# wordclock_frame_led_pcb.net
KiCad netlist of a schematic drawn in EAGLE
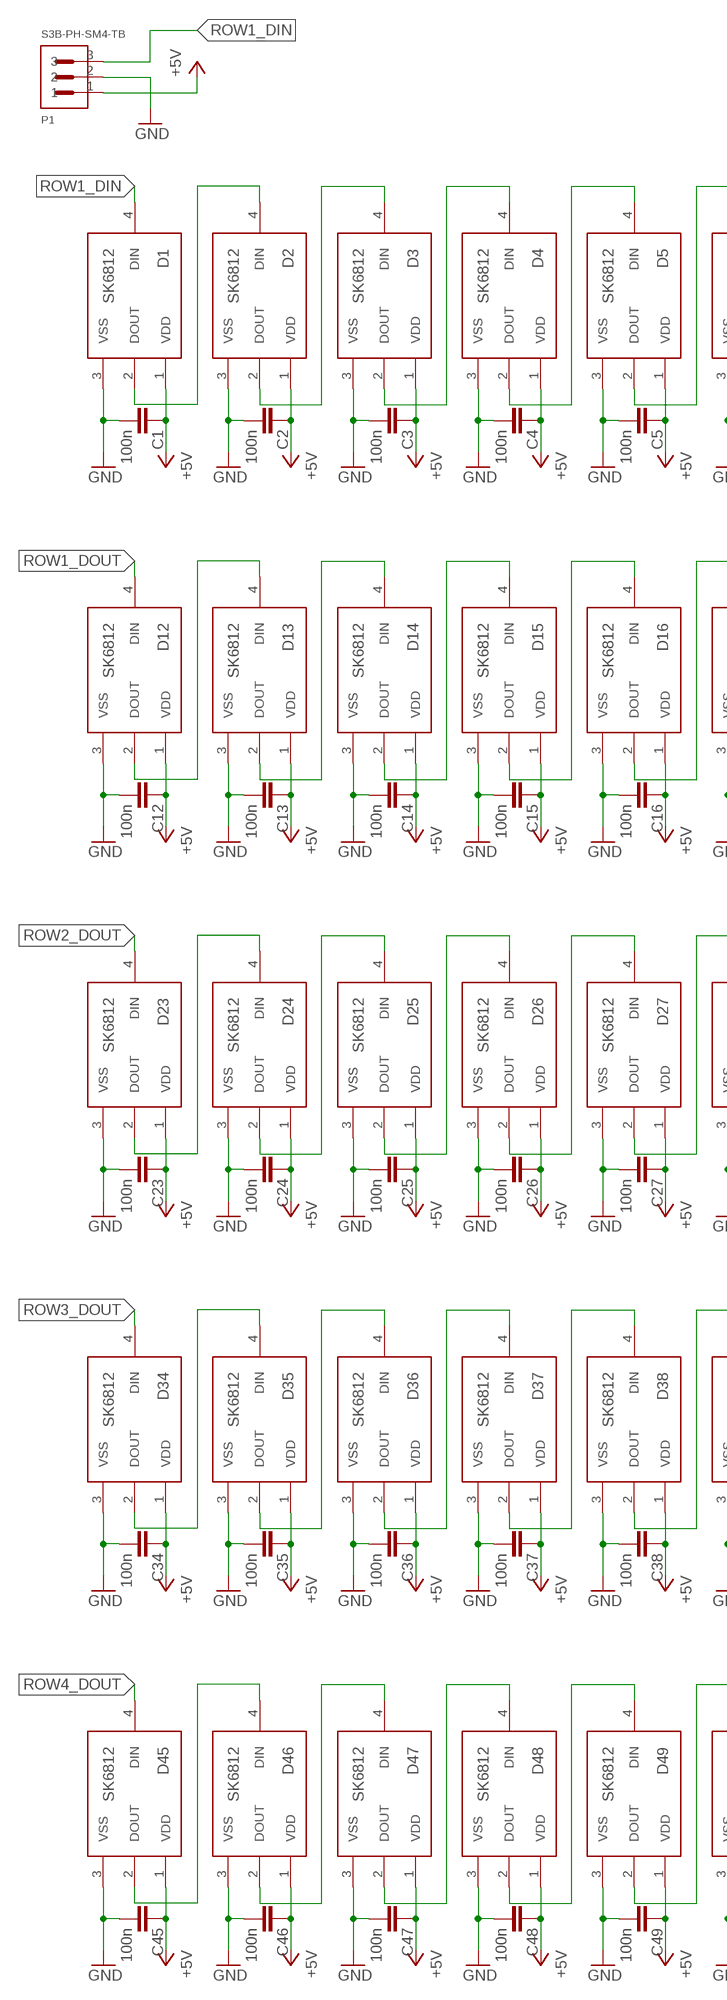
[diagram p0: schematic, sheet 1, part 1 of 2]
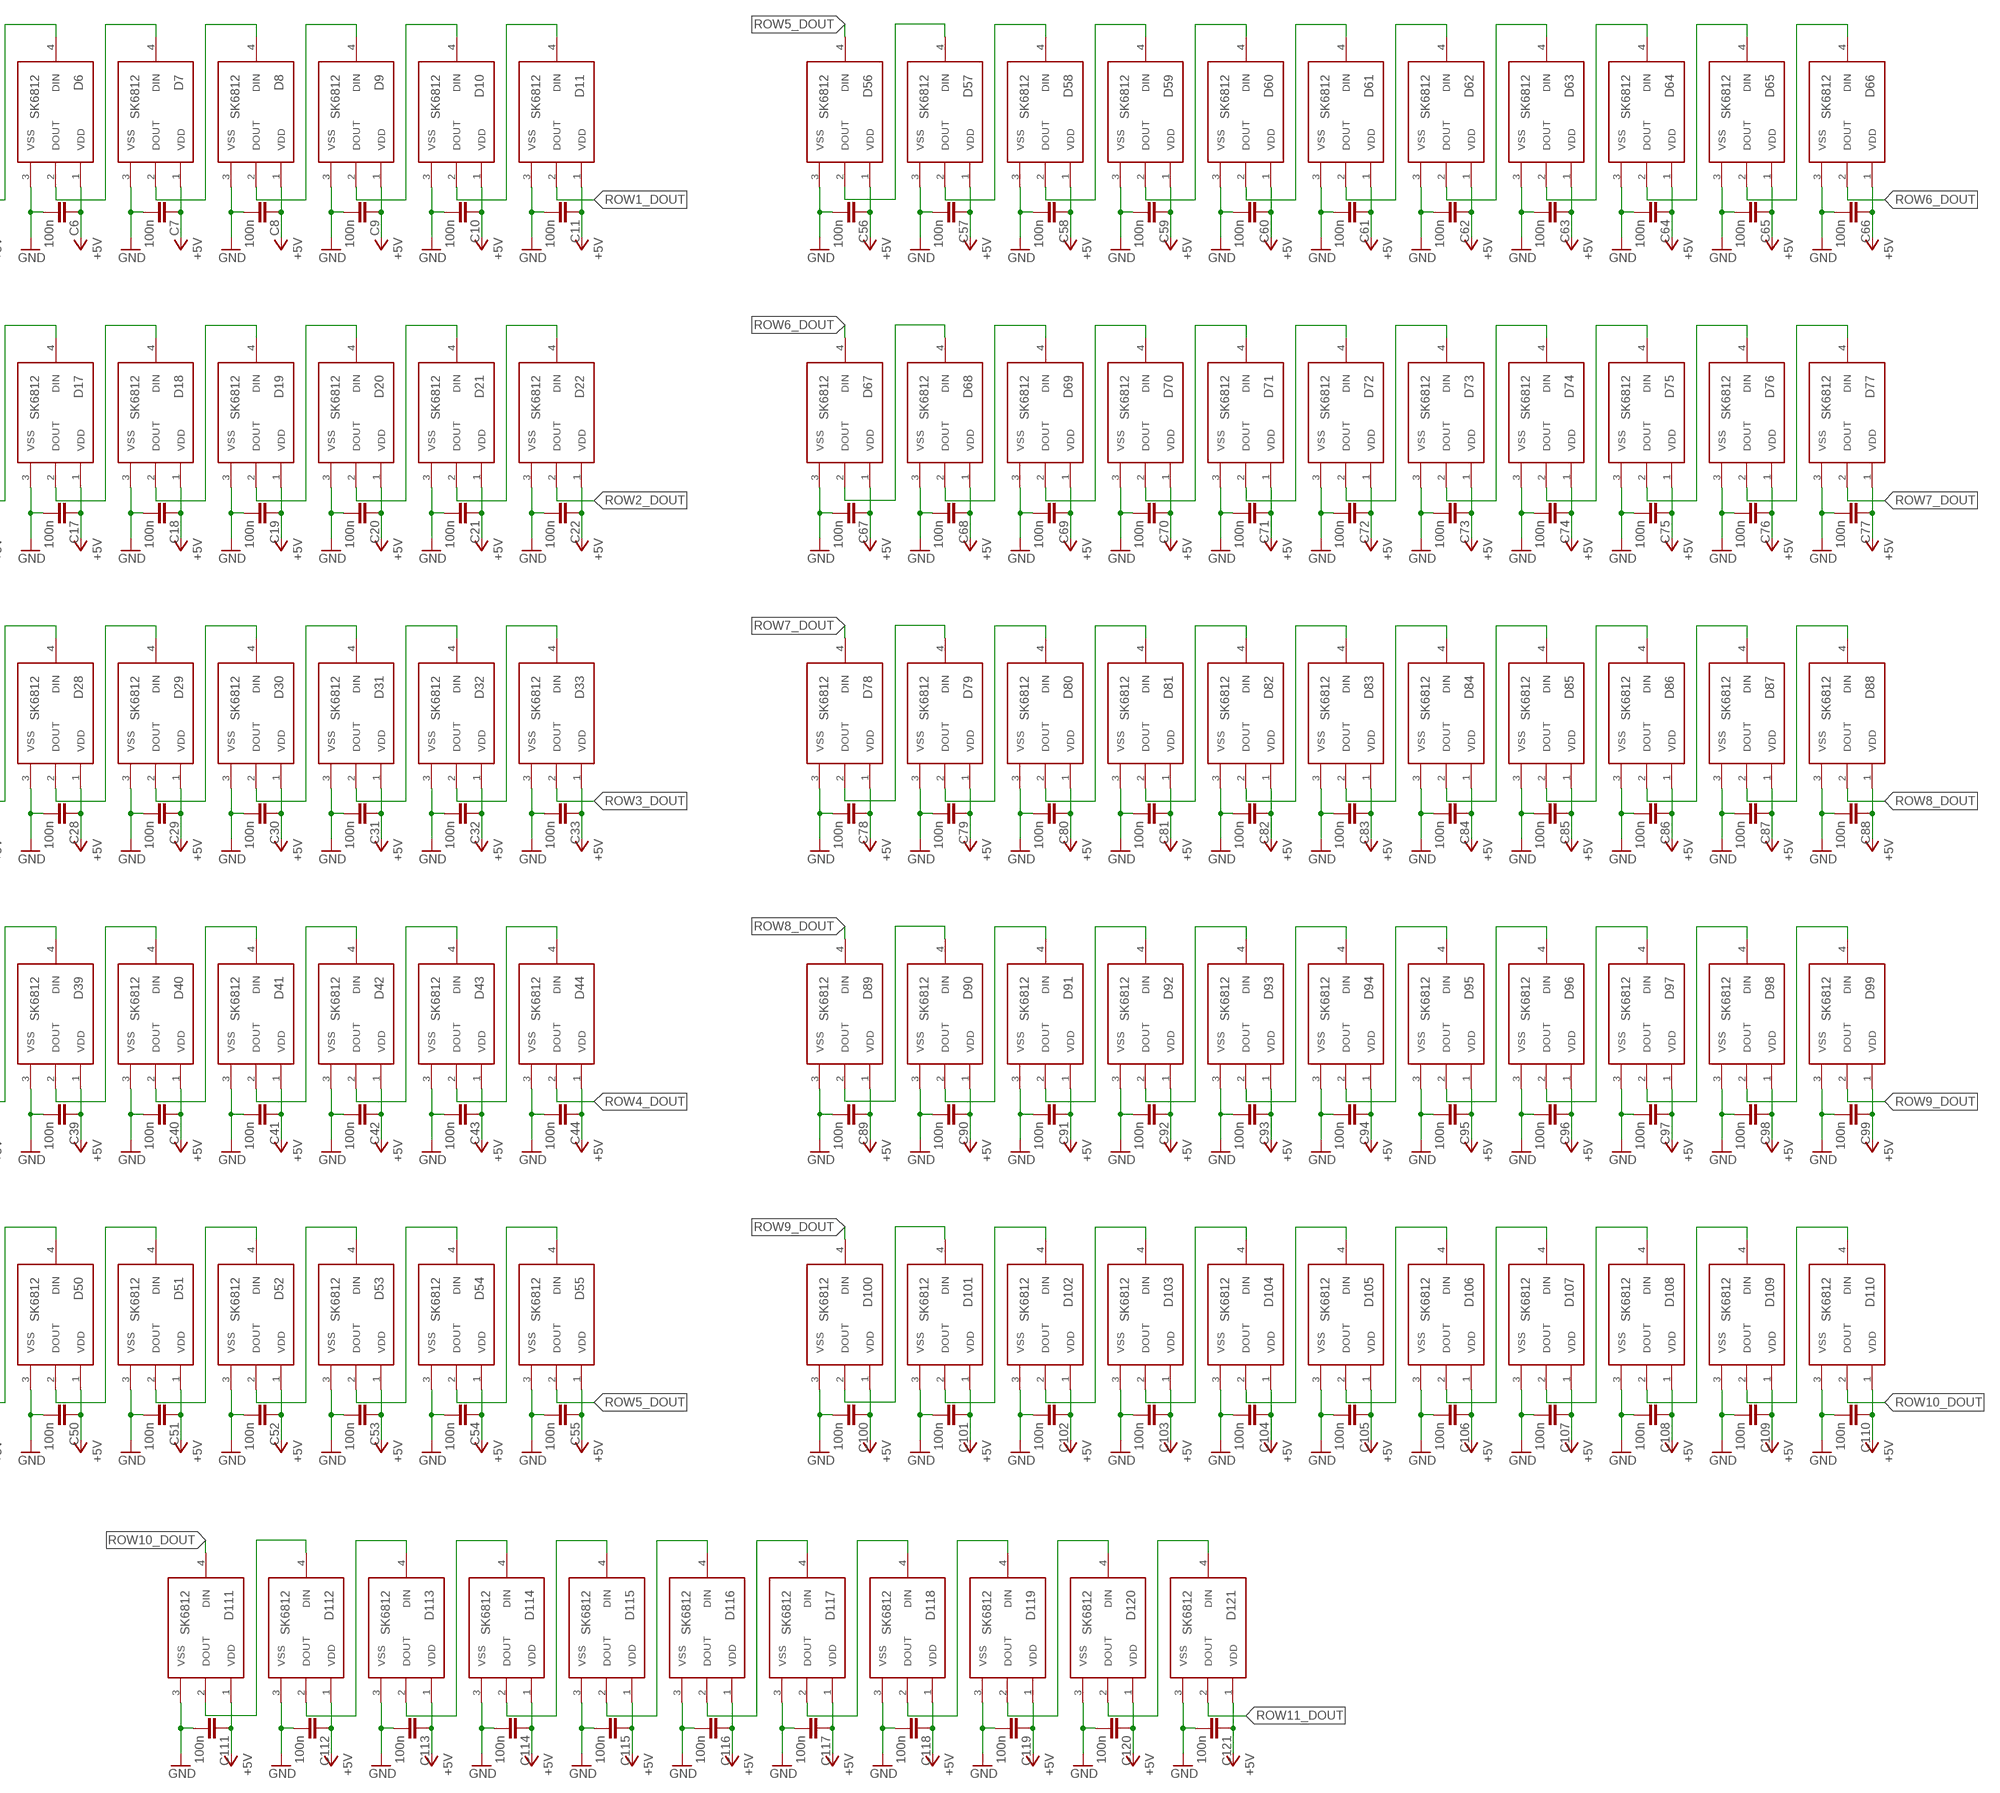
[diagram p1: schematic, sheet 1, part 2 of 2]

(export (version "E")
  (design (tool "Eeschema 10.0.6"))
  (components
    (comp (ref "C1")
      (value "100n")
      (footprint "eagle-import:C0603")
      (libsource (lib "eagle-import") (part "C-EUC0603"))
    )
    (comp (ref "C2")
      (value "100n")
      (footprint "eagle-import:C0603")
      (libsource (lib "eagle-import") (part "C-EUC0603"))
    )
    (comp (ref "C3")
      (value "100n")
      (footprint "eagle-import:C0603")
      (libsource (lib "eagle-import") (part "C-EUC0603"))
    )
    (comp (ref "C4")
      (value "100n")
      (footprint "eagle-import:C0603")
      (libsource (lib "eagle-import") (part "C-EUC0603"))
    )
    (comp (ref "C5")
      (value "100n")
      (footprint "eagle-import:C0603")
      (libsource (lib "eagle-import") (part "C-EUC0603"))
    )
    (comp (ref "C6")
      (value "100n")
      (footprint "eagle-import:C0603")
      (libsource (lib "eagle-import") (part "C-EUC0603"))
    )
    (comp (ref "C7")
      (value "100n")
      (footprint "eagle-import:C0603")
      (libsource (lib "eagle-import") (part "C-EUC0603"))
    )
    (comp (ref "C8")
      (value "100n")
      (footprint "eagle-import:C0603")
      (libsource (lib "eagle-import") (part "C-EUC0603"))
    )
    (comp (ref "C9")
      (value "100n")
      (footprint "eagle-import:C0603")
      (libsource (lib "eagle-import") (part "C-EUC0603"))
    )
    (comp (ref "C10")
      (value "100n")
      (footprint "eagle-import:C0603")
      (libsource (lib "eagle-import") (part "C-EUC0603"))
    )
    (comp (ref "C11")
      (value "100n")
      (footprint "eagle-import:C0603")
      (libsource (lib "eagle-import") (part "C-EUC0603"))
    )
    (comp (ref "C12")
      (value "100n")
      (footprint "eagle-import:C0603")
      (libsource (lib "eagle-import") (part "C-EUC0603"))
    )
    (comp (ref "C13")
      (value "100n")
      (footprint "eagle-import:C0603")
      (libsource (lib "eagle-import") (part "C-EUC0603"))
    )
    (comp (ref "C14")
      (value "100n")
      (footprint "eagle-import:C0603")
      (libsource (lib "eagle-import") (part "C-EUC0603"))
    )
    (comp (ref "C15")
      (value "100n")
      (footprint "eagle-import:C0603")
      (libsource (lib "eagle-import") (part "C-EUC0603"))
    )
    (comp (ref "C16")
      (value "100n")
      (footprint "eagle-import:C0603")
      (libsource (lib "eagle-import") (part "C-EUC0603"))
    )
    (comp (ref "C17")
      (value "100n")
      (footprint "eagle-import:C0603")
      (libsource (lib "eagle-import") (part "C-EUC0603"))
    )
    (comp (ref "C18")
      (value "100n")
      (footprint "eagle-import:C0603")
      (libsource (lib "eagle-import") (part "C-EUC0603"))
    )
    (comp (ref "C19")
      (value "100n")
      (footprint "eagle-import:C0603")
      (libsource (lib "eagle-import") (part "C-EUC0603"))
    )
    (comp (ref "C20")
      (value "100n")
      (footprint "eagle-import:C0603")
      (libsource (lib "eagle-import") (part "C-EUC0603"))
    )
    (comp (ref "C21")
      (value "100n")
      (footprint "eagle-import:C0603")
      (libsource (lib "eagle-import") (part "C-EUC0603"))
    )
    (comp (ref "C22")
      (value "100n")
      (footprint "eagle-import:C0603")
      (libsource (lib "eagle-import") (part "C-EUC0603"))
    )
    (comp (ref "C23")
      (value "100n")
      (footprint "eagle-import:C0603")
      (libsource (lib "eagle-import") (part "C-EUC0603"))
    )
    (comp (ref "C24")
      (value "100n")
      (footprint "eagle-import:C0603")
      (libsource (lib "eagle-import") (part "C-EUC0603"))
    )
    (comp (ref "C25")
      (value "100n")
      (footprint "eagle-import:C0603")
      (libsource (lib "eagle-import") (part "C-EUC0603"))
    )
    (comp (ref "C26")
      (value "100n")
      (footprint "eagle-import:C0603")
      (libsource (lib "eagle-import") (part "C-EUC0603"))
    )
    (comp (ref "C27")
      (value "100n")
      (footprint "eagle-import:C0603")
      (libsource (lib "eagle-import") (part "C-EUC0603"))
    )
    (comp (ref "C28")
      (value "100n")
      (footprint "eagle-import:C0603")
      (libsource (lib "eagle-import") (part "C-EUC0603"))
    )
    (comp (ref "C29")
      (value "100n")
      (footprint "eagle-import:C0603")
      (libsource (lib "eagle-import") (part "C-EUC0603"))
    )
    (comp (ref "C30")
      (value "100n")
      (footprint "eagle-import:C0603")
      (libsource (lib "eagle-import") (part "C-EUC0603"))
    )
    (comp (ref "C31")
      (value "100n")
      (footprint "eagle-import:C0603")
      (libsource (lib "eagle-import") (part "C-EUC0603"))
    )
    (comp (ref "C32")
      (value "100n")
      (footprint "eagle-import:C0603")
      (libsource (lib "eagle-import") (part "C-EUC0603"))
    )
    (comp (ref "C33")
      (value "100n")
      (footprint "eagle-import:C0603")
      (libsource (lib "eagle-import") (part "C-EUC0603"))
    )
    (comp (ref "C34")
      (value "100n")
      (footprint "eagle-import:C0603")
      (libsource (lib "eagle-import") (part "C-EUC0603"))
    )
    (comp (ref "C35")
      (value "100n")
      (footprint "eagle-import:C0603")
      (libsource (lib "eagle-import") (part "C-EUC0603"))
    )
    (comp (ref "C36")
      (value "100n")
      (footprint "eagle-import:C0603")
      (libsource (lib "eagle-import") (part "C-EUC0603"))
    )
    (comp (ref "C37")
      (value "100n")
      (footprint "eagle-import:C0603")
      (libsource (lib "eagle-import") (part "C-EUC0603"))
    )
    (comp (ref "C38")
      (value "100n")
      (footprint "eagle-import:C0603")
      (libsource (lib "eagle-import") (part "C-EUC0603"))
    )
    (comp (ref "C39")
      (value "100n")
      (footprint "eagle-import:C0603")
      (libsource (lib "eagle-import") (part "C-EUC0603"))
    )
    (comp (ref "C40")
      (value "100n")
      (footprint "eagle-import:C0603")
      (libsource (lib "eagle-import") (part "C-EUC0603"))
    )
    (comp (ref "C41")
      (value "100n")
      (footprint "eagle-import:C0603")
      (libsource (lib "eagle-import") (part "C-EUC0603"))
    )
    (comp (ref "C42")
      (value "100n")
      (footprint "eagle-import:C0603")
      (libsource (lib "eagle-import") (part "C-EUC0603"))
    )
    (comp (ref "C43")
      (value "100n")
      (footprint "eagle-import:C0603")
      (libsource (lib "eagle-import") (part "C-EUC0603"))
    )
    (comp (ref "C44")
      (value "100n")
      (footprint "eagle-import:C0603")
      (libsource (lib "eagle-import") (part "C-EUC0603"))
    )
    (comp (ref "C45")
      (value "100n")
      (footprint "eagle-import:C0603")
      (libsource (lib "eagle-import") (part "C-EUC0603"))
    )
    (comp (ref "C46")
      (value "100n")
      (footprint "eagle-import:C0603")
      (libsource (lib "eagle-import") (part "C-EUC0603"))
    )
    (comp (ref "C47")
      (value "100n")
      (footprint "eagle-import:C0603")
      (libsource (lib "eagle-import") (part "C-EUC0603"))
    )
    (comp (ref "C48")
      (value "100n")
      (footprint "eagle-import:C0603")
      (libsource (lib "eagle-import") (part "C-EUC0603"))
    )
    (comp (ref "C49")
      (value "100n")
      (footprint "eagle-import:C0603")
      (libsource (lib "eagle-import") (part "C-EUC0603"))
    )
    (comp (ref "C50")
      (value "100n")
      (footprint "eagle-import:C0603")
      (libsource (lib "eagle-import") (part "C-EUC0603"))
    )
    (comp (ref "C51")
      (value "100n")
      (footprint "eagle-import:C0603")
      (libsource (lib "eagle-import") (part "C-EUC0603"))
    )
    (comp (ref "C52")
      (value "100n")
      (footprint "eagle-import:C0603")
      (libsource (lib "eagle-import") (part "C-EUC0603"))
    )
    (comp (ref "C53")
      (value "100n")
      (footprint "eagle-import:C0603")
      (libsource (lib "eagle-import") (part "C-EUC0603"))
    )
    (comp (ref "C54")
      (value "100n")
      (footprint "eagle-import:C0603")
      (libsource (lib "eagle-import") (part "C-EUC0603"))
    )
    (comp (ref "C55")
      (value "100n")
      (footprint "eagle-import:C0603")
      (libsource (lib "eagle-import") (part "C-EUC0603"))
    )
    (comp (ref "C56")
      (value "100n")
      (footprint "eagle-import:C0603")
      (libsource (lib "eagle-import") (part "C-EUC0603"))
    )
    (comp (ref "C57")
      (value "100n")
      (footprint "eagle-import:C0603")
      (libsource (lib "eagle-import") (part "C-EUC0603"))
    )
    (comp (ref "C58")
      (value "100n")
      (footprint "eagle-import:C0603")
      (libsource (lib "eagle-import") (part "C-EUC0603"))
    )
    (comp (ref "C59")
      (value "100n")
      (footprint "eagle-import:C0603")
      (libsource (lib "eagle-import") (part "C-EUC0603"))
    )
    (comp (ref "C60")
      (value "100n")
      (footprint "eagle-import:C0603")
      (libsource (lib "eagle-import") (part "C-EUC0603"))
    )
    (comp (ref "C61")
      (value "100n")
      (footprint "eagle-import:C0603")
      (libsource (lib "eagle-import") (part "C-EUC0603"))
    )
    (comp (ref "C62")
      (value "100n")
      (footprint "eagle-import:C0603")
      (libsource (lib "eagle-import") (part "C-EUC0603"))
    )
    (comp (ref "C63")
      (value "100n")
      (footprint "eagle-import:C0603")
      (libsource (lib "eagle-import") (part "C-EUC0603"))
    )
    (comp (ref "C64")
      (value "100n")
      (footprint "eagle-import:C0603")
      (libsource (lib "eagle-import") (part "C-EUC0603"))
    )
    (comp (ref "C65")
      (value "100n")
      (footprint "eagle-import:C0603")
      (libsource (lib "eagle-import") (part "C-EUC0603"))
    )
    (comp (ref "C66")
      (value "100n")
      (footprint "eagle-import:C0603")
      (libsource (lib "eagle-import") (part "C-EUC0603"))
    )
    (comp (ref "C67")
      (value "100n")
      (footprint "eagle-import:C0603")
      (libsource (lib "eagle-import") (part "C-EUC0603"))
    )
    (comp (ref "C68")
      (value "100n")
      (footprint "eagle-import:C0603")
      (libsource (lib "eagle-import") (part "C-EUC0603"))
    )
    (comp (ref "C69")
      (value "100n")
      (footprint "eagle-import:C0603")
      (libsource (lib "eagle-import") (part "C-EUC0603"))
    )
    (comp (ref "C70")
      (value "100n")
      (footprint "eagle-import:C0603")
      (libsource (lib "eagle-import") (part "C-EUC0603"))
    )
    (comp (ref "C71")
      (value "100n")
      (footprint "eagle-import:C0603")
      (libsource (lib "eagle-import") (part "C-EUC0603"))
    )
    (comp (ref "C72")
      (value "100n")
      (footprint "eagle-import:C0603")
      (libsource (lib "eagle-import") (part "C-EUC0603"))
    )
    (comp (ref "C73")
      (value "100n")
      (footprint "eagle-import:C0603")
      (libsource (lib "eagle-import") (part "C-EUC0603"))
    )
    (comp (ref "C74")
      (value "100n")
      (footprint "eagle-import:C0603")
      (libsource (lib "eagle-import") (part "C-EUC0603"))
    )
    (comp (ref "C75")
      (value "100n")
      (footprint "eagle-import:C0603")
      (libsource (lib "eagle-import") (part "C-EUC0603"))
    )
    (comp (ref "C76")
      (value "100n")
      (footprint "eagle-import:C0603")
      (libsource (lib "eagle-import") (part "C-EUC0603"))
    )
    (comp (ref "C77")
      (value "100n")
      (footprint "eagle-import:C0603")
      (libsource (lib "eagle-import") (part "C-EUC0603"))
    )
    (comp (ref "C78")
      (value "100n")
      (footprint "eagle-import:C0603")
      (libsource (lib "eagle-import") (part "C-EUC0603"))
    )
    (comp (ref "C79")
      (value "100n")
      (footprint "eagle-import:C0603")
      (libsource (lib "eagle-import") (part "C-EUC0603"))
    )
    (comp (ref "C80")
      (value "100n")
      (footprint "eagle-import:C0603")
      (libsource (lib "eagle-import") (part "C-EUC0603"))
    )
    (comp (ref "C81")
      (value "100n")
      (footprint "eagle-import:C0603")
      (libsource (lib "eagle-import") (part "C-EUC0603"))
    )
    (comp (ref "C82")
      (value "100n")
      (footprint "eagle-import:C0603")
      (libsource (lib "eagle-import") (part "C-EUC0603"))
    )
    (comp (ref "C83")
      (value "100n")
      (footprint "eagle-import:C0603")
      (libsource (lib "eagle-import") (part "C-EUC0603"))
    )
    (comp (ref "C84")
      (value "100n")
      (footprint "eagle-import:C0603")
      (libsource (lib "eagle-import") (part "C-EUC0603"))
    )
    (comp (ref "C85")
      (value "100n")
      (footprint "eagle-import:C0603")
      (libsource (lib "eagle-import") (part "C-EUC0603"))
    )
    (comp (ref "C86")
      (value "100n")
      (footprint "eagle-import:C0603")
      (libsource (lib "eagle-import") (part "C-EUC0603"))
    )
    (comp (ref "C87")
      (value "100n")
      (footprint "eagle-import:C0603")
      (libsource (lib "eagle-import") (part "C-EUC0603"))
    )
    (comp (ref "C88")
      (value "100n")
      (footprint "eagle-import:C0603")
      (libsource (lib "eagle-import") (part "C-EUC0603"))
    )
    (comp (ref "C89")
      (value "100n")
      (footprint "eagle-import:C0603")
      (libsource (lib "eagle-import") (part "C-EUC0603"))
    )
    (comp (ref "C90")
      (value "100n")
      (footprint "eagle-import:C0603")
      (libsource (lib "eagle-import") (part "C-EUC0603"))
    )
    (comp (ref "C91")
      (value "100n")
      (footprint "eagle-import:C0603")
      (libsource (lib "eagle-import") (part "C-EUC0603"))
    )
    (comp (ref "C92")
      (value "100n")
      (footprint "eagle-import:C0603")
      (libsource (lib "eagle-import") (part "C-EUC0603"))
    )
    (comp (ref "C93")
      (value "100n")
      (footprint "eagle-import:C0603")
      (libsource (lib "eagle-import") (part "C-EUC0603"))
    )
    (comp (ref "C94")
      (value "100n")
      (footprint "eagle-import:C0603")
      (libsource (lib "eagle-import") (part "C-EUC0603"))
    )
    (comp (ref "C95")
      (value "100n")
      (footprint "eagle-import:C0603")
      (libsource (lib "eagle-import") (part "C-EUC0603"))
    )
    (comp (ref "C96")
      (value "100n")
      (footprint "eagle-import:C0603")
      (libsource (lib "eagle-import") (part "C-EUC0603"))
    )
    (comp (ref "C97")
      (value "100n")
      (footprint "eagle-import:C0603")
      (libsource (lib "eagle-import") (part "C-EUC0603"))
    )
    (comp (ref "C98")
      (value "100n")
      (footprint "eagle-import:C0603")
      (libsource (lib "eagle-import") (part "C-EUC0603"))
    )
    (comp (ref "C99")
      (value "100n")
      (footprint "eagle-import:C0603")
      (libsource (lib "eagle-import") (part "C-EUC0603"))
    )
    (comp (ref "C100")
      (value "100n")
      (footprint "eagle-import:C0603")
      (libsource (lib "eagle-import") (part "C-EUC0603"))
    )
    (comp (ref "C101")
      (value "100n")
      (footprint "eagle-import:C0603")
      (libsource (lib "eagle-import") (part "C-EUC0603"))
    )
    (comp (ref "C102")
      (value "100n")
      (footprint "eagle-import:C0603")
      (libsource (lib "eagle-import") (part "C-EUC0603"))
    )
    (comp (ref "C103")
      (value "100n")
      (footprint "eagle-import:C0603")
      (libsource (lib "eagle-import") (part "C-EUC0603"))
    )
    (comp (ref "C104")
      (value "100n")
      (footprint "eagle-import:C0603")
      (libsource (lib "eagle-import") (part "C-EUC0603"))
    )
    (comp (ref "C105")
      (value "100n")
      (footprint "eagle-import:C0603")
      (libsource (lib "eagle-import") (part "C-EUC0603"))
    )
    (comp (ref "C106")
      (value "100n")
      (footprint "eagle-import:C0603")
      (libsource (lib "eagle-import") (part "C-EUC0603"))
    )
    (comp (ref "C107")
      (value "100n")
      (footprint "eagle-import:C0603")
      (libsource (lib "eagle-import") (part "C-EUC0603"))
    )
    (comp (ref "C108")
      (value "100n")
      (footprint "eagle-import:C0603")
      (libsource (lib "eagle-import") (part "C-EUC0603"))
    )
    (comp (ref "C109")
      (value "100n")
      (footprint "eagle-import:C0603")
      (libsource (lib "eagle-import") (part "C-EUC0603"))
    )
    (comp (ref "C110")
      (value "100n")
      (footprint "eagle-import:C0603")
      (libsource (lib "eagle-import") (part "C-EUC0603"))
    )
    (comp (ref "C111")
      (value "100n")
      (footprint "eagle-import:C0603")
      (libsource (lib "eagle-import") (part "C-EUC0603"))
    )
    (comp (ref "C112")
      (value "100n")
      (footprint "eagle-import:C0603")
      (libsource (lib "eagle-import") (part "C-EUC0603"))
    )
    (comp (ref "C113")
      (value "100n")
      (footprint "eagle-import:C0603")
      (libsource (lib "eagle-import") (part "C-EUC0603"))
    )
    (comp (ref "C114")
      (value "100n")
      (footprint "eagle-import:C0603")
      (libsource (lib "eagle-import") (part "C-EUC0603"))
    )
    (comp (ref "C115")
      (value "100n")
      (footprint "eagle-import:C0603")
      (libsource (lib "eagle-import") (part "C-EUC0603"))
    )
    (comp (ref "C116")
      (value "100n")
      (footprint "eagle-import:C0603")
      (libsource (lib "eagle-import") (part "C-EUC0603"))
    )
    (comp (ref "C117")
      (value "100n")
      (footprint "eagle-import:C0603")
      (libsource (lib "eagle-import") (part "C-EUC0603"))
    )
    (comp (ref "C118")
      (value "100n")
      (footprint "eagle-import:C0603")
      (libsource (lib "eagle-import") (part "C-EUC0603"))
    )
    (comp (ref "C119")
      (value "100n")
      (footprint "eagle-import:C0603")
      (libsource (lib "eagle-import") (part "C-EUC0603"))
    )
    (comp (ref "C120")
      (value "100n")
      (footprint "eagle-import:C0603")
      (libsource (lib "eagle-import") (part "C-EUC0603"))
    )
    (comp (ref "C121")
      (value "100n")
      (footprint "eagle-import:C0603")
      (libsource (lib "eagle-import") (part "C-EUC0603"))
    )
    (comp (ref "D1")
      (value "SK6812")
      (footprint "eagle-import:LED_SK6812")
      (fields (field (name "MF") "Shenzhen LED Color Optoelectronic Inc."))
      (libsource (lib "eagle-import") (part "SK6812"))
    )
    (comp (ref "D2")
      (value "SK6812")
      (footprint "eagle-import:LED_SK6812")
      (fields (field (name "MF") "Shenzhen LED Color Optoelectronic Inc."))
      (libsource (lib "eagle-import") (part "SK6812"))
    )
    (comp (ref "D3")
      (value "SK6812")
      (footprint "eagle-import:LED_SK6812")
      (fields (field (name "MF") "Shenzhen LED Color Optoelectronic Inc."))
      (libsource (lib "eagle-import") (part "SK6812"))
    )
    (comp (ref "D4")
      (value "SK6812")
      (footprint "eagle-import:LED_SK6812")
      (fields (field (name "MF") "Shenzhen LED Color Optoelectronic Inc."))
      (libsource (lib "eagle-import") (part "SK6812"))
    )
    (comp (ref "D5")
      (value "SK6812")
      (footprint "eagle-import:LED_SK6812")
      (fields (field (name "MF") "Shenzhen LED Color Optoelectronic Inc."))
      (libsource (lib "eagle-import") (part "SK6812"))
    )
    (comp (ref "D6")
      (value "SK6812")
      (footprint "eagle-import:LED_SK6812")
      (fields (field (name "MF") "Shenzhen LED Color Optoelectronic Inc."))
      (libsource (lib "eagle-import") (part "SK6812"))
    )
    (comp (ref "D7")
      (value "SK6812")
      (footprint "eagle-import:LED_SK6812")
      (fields (field (name "MF") "Shenzhen LED Color Optoelectronic Inc."))
      (libsource (lib "eagle-import") (part "SK6812"))
    )
    (comp (ref "D8")
      (value "SK6812")
      (footprint "eagle-import:LED_SK6812")
      (fields (field (name "MF") "Shenzhen LED Color Optoelectronic Inc."))
      (libsource (lib "eagle-import") (part "SK6812"))
    )
    (comp (ref "D9")
      (value "SK6812")
      (footprint "eagle-import:LED_SK6812")
      (fields (field (name "MF") "Shenzhen LED Color Optoelectronic Inc."))
      (libsource (lib "eagle-import") (part "SK6812"))
    )
    (comp (ref "D10")
      (value "SK6812")
      (footprint "eagle-import:LED_SK6812")
      (fields (field (name "MF") "Shenzhen LED Color Optoelectronic Inc."))
      (libsource (lib "eagle-import") (part "SK6812"))
    )
    (comp (ref "D11")
      (value "SK6812")
      (footprint "eagle-import:LED_SK6812")
      (fields (field (name "MF") "Shenzhen LED Color Optoelectronic Inc."))
      (libsource (lib "eagle-import") (part "SK6812"))
    )
    (comp (ref "D12")
      (value "SK6812")
      (footprint "eagle-import:LED_SK6812")
      (fields (field (name "MF") "Shenzhen LED Color Optoelectronic Inc."))
      (libsource (lib "eagle-import") (part "SK6812"))
    )
    (comp (ref "D13")
      (value "SK6812")
      (footprint "eagle-import:LED_SK6812")
      (fields (field (name "MF") "Shenzhen LED Color Optoelectronic Inc."))
      (libsource (lib "eagle-import") (part "SK6812"))
    )
    (comp (ref "D14")
      (value "SK6812")
      (footprint "eagle-import:LED_SK6812")
      (fields (field (name "MF") "Shenzhen LED Color Optoelectronic Inc."))
      (libsource (lib "eagle-import") (part "SK6812"))
    )
    (comp (ref "D15")
      (value "SK6812")
      (footprint "eagle-import:LED_SK6812")
      (fields (field (name "MF") "Shenzhen LED Color Optoelectronic Inc."))
      (libsource (lib "eagle-import") (part "SK6812"))
    )
    (comp (ref "D16")
      (value "SK6812")
      (footprint "eagle-import:LED_SK6812")
      (fields (field (name "MF") "Shenzhen LED Color Optoelectronic Inc."))
      (libsource (lib "eagle-import") (part "SK6812"))
    )
    (comp (ref "D17")
      (value "SK6812")
      (footprint "eagle-import:LED_SK6812")
      (fields (field (name "MF") "Shenzhen LED Color Optoelectronic Inc."))
      (libsource (lib "eagle-import") (part "SK6812"))
    )
    (comp (ref "D18")
      (value "SK6812")
      (footprint "eagle-import:LED_SK6812")
      (fields (field (name "MF") "Shenzhen LED Color Optoelectronic Inc."))
      (libsource (lib "eagle-import") (part "SK6812"))
    )
    (comp (ref "D19")
      (value "SK6812")
      (footprint "eagle-import:LED_SK6812")
      (fields (field (name "MF") "Shenzhen LED Color Optoelectronic Inc."))
      (libsource (lib "eagle-import") (part "SK6812"))
    )
    (comp (ref "D20")
      (value "SK6812")
      (footprint "eagle-import:LED_SK6812")
      (fields (field (name "MF") "Shenzhen LED Color Optoelectronic Inc."))
      (libsource (lib "eagle-import") (part "SK6812"))
    )
    (comp (ref "D21")
      (value "SK6812")
      (footprint "eagle-import:LED_SK6812")
      (fields (field (name "MF") "Shenzhen LED Color Optoelectronic Inc."))
      (libsource (lib "eagle-import") (part "SK6812"))
    )
    (comp (ref "D22")
      (value "SK6812")
      (footprint "eagle-import:LED_SK6812")
      (fields (field (name "MF") "Shenzhen LED Color Optoelectronic Inc."))
      (libsource (lib "eagle-import") (part "SK6812"))
    )
    (comp (ref "D23")
      (value "SK6812")
      (footprint "eagle-import:LED_SK6812")
      (fields (field (name "MF") "Shenzhen LED Color Optoelectronic Inc."))
      (libsource (lib "eagle-import") (part "SK6812"))
    )
    (comp (ref "D24")
      (value "SK6812")
      (footprint "eagle-import:LED_SK6812")
      (fields (field (name "MF") "Shenzhen LED Color Optoelectronic Inc."))
      (libsource (lib "eagle-import") (part "SK6812"))
    )
    (comp (ref "D25")
      (value "SK6812")
      (footprint "eagle-import:LED_SK6812")
      (fields (field (name "MF") "Shenzhen LED Color Optoelectronic Inc."))
      (libsource (lib "eagle-import") (part "SK6812"))
    )
    (comp (ref "D26")
      (value "SK6812")
      (footprint "eagle-import:LED_SK6812")
      (fields (field (name "MF") "Shenzhen LED Color Optoelectronic Inc."))
      (libsource (lib "eagle-import") (part "SK6812"))
    )
    (comp (ref "D27")
      (value "SK6812")
      (footprint "eagle-import:LED_SK6812")
      (fields (field (name "MF") "Shenzhen LED Color Optoelectronic Inc."))
      (libsource (lib "eagle-import") (part "SK6812"))
    )
    (comp (ref "D28")
      (value "SK6812")
      (footprint "eagle-import:LED_SK6812")
      (fields (field (name "MF") "Shenzhen LED Color Optoelectronic Inc."))
      (libsource (lib "eagle-import") (part "SK6812"))
    )
    (comp (ref "D29")
      (value "SK6812")
      (footprint "eagle-import:LED_SK6812")
      (fields (field (name "MF") "Shenzhen LED Color Optoelectronic Inc."))
      (libsource (lib "eagle-import") (part "SK6812"))
    )
    (comp (ref "D30")
      (value "SK6812")
      (footprint "eagle-import:LED_SK6812")
      (fields (field (name "MF") "Shenzhen LED Color Optoelectronic Inc."))
      (libsource (lib "eagle-import") (part "SK6812"))
    )
    (comp (ref "D31")
      (value "SK6812")
      (footprint "eagle-import:LED_SK6812")
      (fields (field (name "MF") "Shenzhen LED Color Optoelectronic Inc."))
      (libsource (lib "eagle-import") (part "SK6812"))
    )
    (comp (ref "D32")
      (value "SK6812")
      (footprint "eagle-import:LED_SK6812")
      (fields (field (name "MF") "Shenzhen LED Color Optoelectronic Inc."))
      (libsource (lib "eagle-import") (part "SK6812"))
    )
    (comp (ref "D33")
      (value "SK6812")
      (footprint "eagle-import:LED_SK6812")
      (fields (field (name "MF") "Shenzhen LED Color Optoelectronic Inc."))
      (libsource (lib "eagle-import") (part "SK6812"))
    )
    (comp (ref "D34")
      (value "SK6812")
      (footprint "eagle-import:LED_SK6812")
      (fields (field (name "MF") "Shenzhen LED Color Optoelectronic Inc."))
      (libsource (lib "eagle-import") (part "SK6812"))
    )
    (comp (ref "D35")
      (value "SK6812")
      (footprint "eagle-import:LED_SK6812")
      (fields (field (name "MF") "Shenzhen LED Color Optoelectronic Inc."))
      (libsource (lib "eagle-import") (part "SK6812"))
    )
    (comp (ref "D36")
      (value "SK6812")
      (footprint "eagle-import:LED_SK6812")
      (fields (field (name "MF") "Shenzhen LED Color Optoelectronic Inc."))
      (libsource (lib "eagle-import") (part "SK6812"))
    )
    (comp (ref "D37")
      (value "SK6812")
      (footprint "eagle-import:LED_SK6812")
      (fields (field (name "MF") "Shenzhen LED Color Optoelectronic Inc."))
      (libsource (lib "eagle-import") (part "SK6812"))
    )
    (comp (ref "D38")
      (value "SK6812")
      (footprint "eagle-import:LED_SK6812")
      (fields (field (name "MF") "Shenzhen LED Color Optoelectronic Inc."))
      (libsource (lib "eagle-import") (part "SK6812"))
    )
    (comp (ref "D39")
      (value "SK6812")
      (footprint "eagle-import:LED_SK6812")
      (fields (field (name "MF") "Shenzhen LED Color Optoelectronic Inc."))
      (libsource (lib "eagle-import") (part "SK6812"))
    )
    (comp (ref "D40")
      (value "SK6812")
      (footprint "eagle-import:LED_SK6812")
      (fields (field (name "MF") "Shenzhen LED Color Optoelectronic Inc."))
      (libsource (lib "eagle-import") (part "SK6812"))
    )
    (comp (ref "D41")
      (value "SK6812")
      (footprint "eagle-import:LED_SK6812")
      (fields (field (name "MF") "Shenzhen LED Color Optoelectronic Inc."))
      (libsource (lib "eagle-import") (part "SK6812"))
    )
    (comp (ref "D42")
      (value "SK6812")
      (footprint "eagle-import:LED_SK6812")
      (fields (field (name "MF") "Shenzhen LED Color Optoelectronic Inc."))
      (libsource (lib "eagle-import") (part "SK6812"))
    )
    (comp (ref "D43")
      (value "SK6812")
      (footprint "eagle-import:LED_SK6812")
      (fields (field (name "MF") "Shenzhen LED Color Optoelectronic Inc."))
      (libsource (lib "eagle-import") (part "SK6812"))
    )
    (comp (ref "D44")
      (value "SK6812")
      (footprint "eagle-import:LED_SK6812")
      (fields (field (name "MF") "Shenzhen LED Color Optoelectronic Inc."))
      (libsource (lib "eagle-import") (part "SK6812"))
    )
    (comp (ref "D45")
      (value "SK6812")
      (footprint "eagle-import:LED_SK6812")
      (fields (field (name "MF") "Shenzhen LED Color Optoelectronic Inc."))
      (libsource (lib "eagle-import") (part "SK6812"))
    )
    (comp (ref "D46")
      (value "SK6812")
      (footprint "eagle-import:LED_SK6812")
      (fields (field (name "MF") "Shenzhen LED Color Optoelectronic Inc."))
      (libsource (lib "eagle-import") (part "SK6812"))
    )
    (comp (ref "D47")
      (value "SK6812")
      (footprint "eagle-import:LED_SK6812")
      (fields (field (name "MF") "Shenzhen LED Color Optoelectronic Inc."))
      (libsource (lib "eagle-import") (part "SK6812"))
    )
    (comp (ref "D48")
      (value "SK6812")
      (footprint "eagle-import:LED_SK6812")
      (fields (field (name "MF") "Shenzhen LED Color Optoelectronic Inc."))
      (libsource (lib "eagle-import") (part "SK6812"))
    )
    (comp (ref "D49")
      (value "SK6812")
      (footprint "eagle-import:LED_SK6812")
      (fields (field (name "MF") "Shenzhen LED Color Optoelectronic Inc."))
      (libsource (lib "eagle-import") (part "SK6812"))
    )
    (comp (ref "D50")
      (value "SK6812")
      (footprint "eagle-import:LED_SK6812")
      (fields (field (name "MF") "Shenzhen LED Color Optoelectronic Inc."))
      (libsource (lib "eagle-import") (part "SK6812"))
    )
    (comp (ref "D51")
      (value "SK6812")
      (footprint "eagle-import:LED_SK6812")
      (fields (field (name "MF") "Shenzhen LED Color Optoelectronic Inc."))
      (libsource (lib "eagle-import") (part "SK6812"))
    )
    (comp (ref "D52")
      (value "SK6812")
      (footprint "eagle-import:LED_SK6812")
      (fields (field (name "MF") "Shenzhen LED Color Optoelectronic Inc."))
      (libsource (lib "eagle-import") (part "SK6812"))
    )
    (comp (ref "D53")
      (value "SK6812")
      (footprint "eagle-import:LED_SK6812")
      (fields (field (name "MF") "Shenzhen LED Color Optoelectronic Inc."))
      (libsource (lib "eagle-import") (part "SK6812"))
    )
    (comp (ref "D54")
      (value "SK6812")
      (footprint "eagle-import:LED_SK6812")
      (fields (field (name "MF") "Shenzhen LED Color Optoelectronic Inc."))
      (libsource (lib "eagle-import") (part "SK6812"))
    )
    (comp (ref "D55")
      (value "SK6812")
      (footprint "eagle-import:LED_SK6812")
      (fields (field (name "MF") "Shenzhen LED Color Optoelectronic Inc."))
      (libsource (lib "eagle-import") (part "SK6812"))
    )
    (comp (ref "D56")
      (value "SK6812")
      (footprint "eagle-import:LED_SK6812")
      (fields (field (name "MF") "Shenzhen LED Color Optoelectronic Inc."))
      (libsource (lib "eagle-import") (part "SK6812"))
    )
    (comp (ref "D57")
      (value "SK6812")
      (footprint "eagle-import:LED_SK6812")
      (fields (field (name "MF") "Shenzhen LED Color Optoelectronic Inc."))
      (libsource (lib "eagle-import") (part "SK6812"))
    )
    (comp (ref "D58")
      (value "SK6812")
      (footprint "eagle-import:LED_SK6812")
      (fields (field (name "MF") "Shenzhen LED Color Optoelectronic Inc."))
      (libsource (lib "eagle-import") (part "SK6812"))
    )
    (comp (ref "D59")
      (value "SK6812")
      (footprint "eagle-import:LED_SK6812")
      (fields (field (name "MF") "Shenzhen LED Color Optoelectronic Inc."))
      (libsource (lib "eagle-import") (part "SK6812"))
    )
    (comp (ref "D60")
      (value "SK6812")
      (footprint "eagle-import:LED_SK6812")
      (fields (field (name "MF") "Shenzhen LED Color Optoelectronic Inc."))
      (libsource (lib "eagle-import") (part "SK6812"))
    )
    (comp (ref "D61")
      (value "SK6812")
      (footprint "eagle-import:LED_SK6812")
      (fields (field (name "MF") "Shenzhen LED Color Optoelectronic Inc."))
      (libsource (lib "eagle-import") (part "SK6812"))
    )
    (comp (ref "D62")
      (value "SK6812")
      (footprint "eagle-import:LED_SK6812")
      (fields (field (name "MF") "Shenzhen LED Color Optoelectronic Inc."))
      (libsource (lib "eagle-import") (part "SK6812"))
    )
    (comp (ref "D63")
      (value "SK6812")
      (footprint "eagle-import:LED_SK6812")
      (fields (field (name "MF") "Shenzhen LED Color Optoelectronic Inc."))
      (libsource (lib "eagle-import") (part "SK6812"))
    )
    (comp (ref "D64")
      (value "SK6812")
      (footprint "eagle-import:LED_SK6812")
      (fields (field (name "MF") "Shenzhen LED Color Optoelectronic Inc."))
      (libsource (lib "eagle-import") (part "SK6812"))
    )
    (comp (ref "D65")
      (value "SK6812")
      (footprint "eagle-import:LED_SK6812")
      (fields (field (name "MF") "Shenzhen LED Color Optoelectronic Inc."))
      (libsource (lib "eagle-import") (part "SK6812"))
    )
    (comp (ref "D66")
      (value "SK6812")
      (footprint "eagle-import:LED_SK6812")
      (fields (field (name "MF") "Shenzhen LED Color Optoelectronic Inc."))
      (libsource (lib "eagle-import") (part "SK6812"))
    )
    (comp (ref "D67")
      (value "SK6812")
      (footprint "eagle-import:LED_SK6812")
      (fields (field (name "MF") "Shenzhen LED Color Optoelectronic Inc."))
      (libsource (lib "eagle-import") (part "SK6812"))
    )
    (comp (ref "D68")
      (value "SK6812")
      (footprint "eagle-import:LED_SK6812")
      (fields (field (name "MF") "Shenzhen LED Color Optoelectronic Inc."))
      (libsource (lib "eagle-import") (part "SK6812"))
    )
    (comp (ref "D69")
      (value "SK6812")
      (footprint "eagle-import:LED_SK6812")
      (fields (field (name "MF") "Shenzhen LED Color Optoelectronic Inc."))
      (libsource (lib "eagle-import") (part "SK6812"))
    )
    (comp (ref "D70")
      (value "SK6812")
      (footprint "eagle-import:LED_SK6812")
      (fields (field (name "MF") "Shenzhen LED Color Optoelectronic Inc."))
      (libsource (lib "eagle-import") (part "SK6812"))
    )
    (comp (ref "D71")
      (value "SK6812")
      (footprint "eagle-import:LED_SK6812")
      (fields (field (name "MF") "Shenzhen LED Color Optoelectronic Inc."))
      (libsource (lib "eagle-import") (part "SK6812"))
    )
    (comp (ref "D72")
      (value "SK6812")
      (footprint "eagle-import:LED_SK6812")
      (fields (field (name "MF") "Shenzhen LED Color Optoelectronic Inc."))
      (libsource (lib "eagle-import") (part "SK6812"))
    )
    (comp (ref "D73")
      (value "SK6812")
      (footprint "eagle-import:LED_SK6812")
      (fields (field (name "MF") "Shenzhen LED Color Optoelectronic Inc."))
      (libsource (lib "eagle-import") (part "SK6812"))
    )
    (comp (ref "D74")
      (value "SK6812")
      (footprint "eagle-import:LED_SK6812")
      (fields (field (name "MF") "Shenzhen LED Color Optoelectronic Inc."))
      (libsource (lib "eagle-import") (part "SK6812"))
    )
    (comp (ref "D75")
      (value "SK6812")
      (footprint "eagle-import:LED_SK6812")
      (fields (field (name "MF") "Shenzhen LED Color Optoelectronic Inc."))
      (libsource (lib "eagle-import") (part "SK6812"))
    )
    (comp (ref "D76")
      (value "SK6812")
      (footprint "eagle-import:LED_SK6812")
      (fields (field (name "MF") "Shenzhen LED Color Optoelectronic Inc."))
      (libsource (lib "eagle-import") (part "SK6812"))
    )
    (comp (ref "D77")
      (value "SK6812")
      (footprint "eagle-import:LED_SK6812")
      (fields (field (name "MF") "Shenzhen LED Color Optoelectronic Inc."))
      (libsource (lib "eagle-import") (part "SK6812"))
    )
    (comp (ref "D78")
      (value "SK6812")
      (footprint "eagle-import:LED_SK6812")
      (fields (field (name "MF") "Shenzhen LED Color Optoelectronic Inc."))
      (libsource (lib "eagle-import") (part "SK6812"))
    )
    (comp (ref "D79")
      (value "SK6812")
      (footprint "eagle-import:LED_SK6812")
      (fields (field (name "MF") "Shenzhen LED Color Optoelectronic Inc."))
      (libsource (lib "eagle-import") (part "SK6812"))
    )
    (comp (ref "D80")
      (value "SK6812")
      (footprint "eagle-import:LED_SK6812")
      (fields (field (name "MF") "Shenzhen LED Color Optoelectronic Inc."))
      (libsource (lib "eagle-import") (part "SK6812"))
    )
    (comp (ref "D81")
      (value "SK6812")
      (footprint "eagle-import:LED_SK6812")
      (fields (field (name "MF") "Shenzhen LED Color Optoelectronic Inc."))
      (libsource (lib "eagle-import") (part "SK6812"))
    )
    (comp (ref "D82")
      (value "SK6812")
      (footprint "eagle-import:LED_SK6812")
      (fields (field (name "MF") "Shenzhen LED Color Optoelectronic Inc."))
      (libsource (lib "eagle-import") (part "SK6812"))
    )
    (comp (ref "D83")
      (value "SK6812")
      (footprint "eagle-import:LED_SK6812")
      (fields (field (name "MF") "Shenzhen LED Color Optoelectronic Inc."))
      (libsource (lib "eagle-import") (part "SK6812"))
    )
    (comp (ref "D84")
      (value "SK6812")
      (footprint "eagle-import:LED_SK6812")
      (fields (field (name "MF") "Shenzhen LED Color Optoelectronic Inc."))
      (libsource (lib "eagle-import") (part "SK6812"))
    )
    (comp (ref "D85")
      (value "SK6812")
      (footprint "eagle-import:LED_SK6812")
      (fields (field (name "MF") "Shenzhen LED Color Optoelectronic Inc."))
      (libsource (lib "eagle-import") (part "SK6812"))
    )
    (comp (ref "D86")
      (value "SK6812")
      (footprint "eagle-import:LED_SK6812")
      (fields (field (name "MF") "Shenzhen LED Color Optoelectronic Inc."))
      (libsource (lib "eagle-import") (part "SK6812"))
    )
    (comp (ref "D87")
      (value "SK6812")
      (footprint "eagle-import:LED_SK6812")
      (fields (field (name "MF") "Shenzhen LED Color Optoelectronic Inc."))
      (libsource (lib "eagle-import") (part "SK6812"))
    )
    (comp (ref "D88")
      (value "SK6812")
      (footprint "eagle-import:LED_SK6812")
      (fields (field (name "MF") "Shenzhen LED Color Optoelectronic Inc."))
      (libsource (lib "eagle-import") (part "SK6812"))
    )
    (comp (ref "D89")
      (value "SK6812")
      (footprint "eagle-import:LED_SK6812")
      (fields (field (name "MF") "Shenzhen LED Color Optoelectronic Inc."))
      (libsource (lib "eagle-import") (part "SK6812"))
    )
    (comp (ref "D90")
      (value "SK6812")
      (footprint "eagle-import:LED_SK6812")
      (fields (field (name "MF") "Shenzhen LED Color Optoelectronic Inc."))
      (libsource (lib "eagle-import") (part "SK6812"))
    )
    (comp (ref "D91")
      (value "SK6812")
      (footprint "eagle-import:LED_SK6812")
      (fields (field (name "MF") "Shenzhen LED Color Optoelectronic Inc."))
      (libsource (lib "eagle-import") (part "SK6812"))
    )
    (comp (ref "D92")
      (value "SK6812")
      (footprint "eagle-import:LED_SK6812")
      (fields (field (name "MF") "Shenzhen LED Color Optoelectronic Inc."))
      (libsource (lib "eagle-import") (part "SK6812"))
    )
    (comp (ref "D93")
      (value "SK6812")
      (footprint "eagle-import:LED_SK6812")
      (fields (field (name "MF") "Shenzhen LED Color Optoelectronic Inc."))
      (libsource (lib "eagle-import") (part "SK6812"))
    )
    (comp (ref "D94")
      (value "SK6812")
      (footprint "eagle-import:LED_SK6812")
      (fields (field (name "MF") "Shenzhen LED Color Optoelectronic Inc."))
      (libsource (lib "eagle-import") (part "SK6812"))
    )
    (comp (ref "D95")
      (value "SK6812")
      (footprint "eagle-import:LED_SK6812")
      (fields (field (name "MF") "Shenzhen LED Color Optoelectronic Inc."))
      (libsource (lib "eagle-import") (part "SK6812"))
    )
    (comp (ref "D96")
      (value "SK6812")
      (footprint "eagle-import:LED_SK6812")
      (fields (field (name "MF") "Shenzhen LED Color Optoelectronic Inc."))
      (libsource (lib "eagle-import") (part "SK6812"))
    )
    (comp (ref "D97")
      (value "SK6812")
      (footprint "eagle-import:LED_SK6812")
      (fields (field (name "MF") "Shenzhen LED Color Optoelectronic Inc."))
      (libsource (lib "eagle-import") (part "SK6812"))
    )
    (comp (ref "D98")
      (value "SK6812")
      (footprint "eagle-import:LED_SK6812")
      (fields (field (name "MF") "Shenzhen LED Color Optoelectronic Inc."))
      (libsource (lib "eagle-import") (part "SK6812"))
    )
    (comp (ref "D99")
      (value "SK6812")
      (footprint "eagle-import:LED_SK6812")
      (fields (field (name "MF") "Shenzhen LED Color Optoelectronic Inc."))
      (libsource (lib "eagle-import") (part "SK6812"))
    )
    (comp (ref "D100")
      (value "SK6812")
      (footprint "eagle-import:LED_SK6812")
      (fields (field (name "MF") "Shenzhen LED Color Optoelectronic Inc."))
      (libsource (lib "eagle-import") (part "SK6812"))
    )
    (comp (ref "D101")
      (value "SK6812")
      (footprint "eagle-import:LED_SK6812")
      (fields (field (name "MF") "Shenzhen LED Color Optoelectronic Inc."))
      (libsource (lib "eagle-import") (part "SK6812"))
    )
    (comp (ref "D102")
      (value "SK6812")
      (footprint "eagle-import:LED_SK6812")
      (fields (field (name "MF") "Shenzhen LED Color Optoelectronic Inc."))
      (libsource (lib "eagle-import") (part "SK6812"))
    )
    (comp (ref "D103")
      (value "SK6812")
      (footprint "eagle-import:LED_SK6812")
      (fields (field (name "MF") "Shenzhen LED Color Optoelectronic Inc."))
      (libsource (lib "eagle-import") (part "SK6812"))
    )
    (comp (ref "D104")
      (value "SK6812")
      (footprint "eagle-import:LED_SK6812")
      (fields (field (name "MF") "Shenzhen LED Color Optoelectronic Inc."))
      (libsource (lib "eagle-import") (part "SK6812"))
    )
    (comp (ref "D105")
      (value "SK6812")
      (footprint "eagle-import:LED_SK6812")
      (fields (field (name "MF") "Shenzhen LED Color Optoelectronic Inc."))
      (libsource (lib "eagle-import") (part "SK6812"))
    )
    (comp (ref "D106")
      (value "SK6812")
      (footprint "eagle-import:LED_SK6812")
      (fields (field (name "MF") "Shenzhen LED Color Optoelectronic Inc."))
      (libsource (lib "eagle-import") (part "SK6812"))
    )
    (comp (ref "D107")
      (value "SK6812")
      (footprint "eagle-import:LED_SK6812")
      (fields (field (name "MF") "Shenzhen LED Color Optoelectronic Inc."))
      (libsource (lib "eagle-import") (part "SK6812"))
    )
    (comp (ref "D108")
      (value "SK6812")
      (footprint "eagle-import:LED_SK6812")
      (fields (field (name "MF") "Shenzhen LED Color Optoelectronic Inc."))
      (libsource (lib "eagle-import") (part "SK6812"))
    )
    (comp (ref "D109")
      (value "SK6812")
      (footprint "eagle-import:LED_SK6812")
      (fields (field (name "MF") "Shenzhen LED Color Optoelectronic Inc."))
      (libsource (lib "eagle-import") (part "SK6812"))
    )
    (comp (ref "D110")
      (value "SK6812")
      (footprint "eagle-import:LED_SK6812")
      (fields (field (name "MF") "Shenzhen LED Color Optoelectronic Inc."))
      (libsource (lib "eagle-import") (part "SK6812"))
    )
    (comp (ref "D111")
      (value "SK6812")
      (footprint "eagle-import:LED_SK6812")
      (fields (field (name "MF") "Shenzhen LED Color Optoelectronic Inc."))
      (libsource (lib "eagle-import") (part "SK6812"))
    )
    (comp (ref "D112")
      (value "SK6812")
      (footprint "eagle-import:LED_SK6812")
      (fields (field (name "MF") "Shenzhen LED Color Optoelectronic Inc."))
      (libsource (lib "eagle-import") (part "SK6812"))
    )
    (comp (ref "D113")
      (value "SK6812")
      (footprint "eagle-import:LED_SK6812")
      (fields (field (name "MF") "Shenzhen LED Color Optoelectronic Inc."))
      (libsource (lib "eagle-import") (part "SK6812"))
    )
    (comp (ref "D114")
      (value "SK6812")
      (footprint "eagle-import:LED_SK6812")
      (fields (field (name "MF") "Shenzhen LED Color Optoelectronic Inc."))
      (libsource (lib "eagle-import") (part "SK6812"))
    )
    (comp (ref "D115")
      (value "SK6812")
      (footprint "eagle-import:LED_SK6812")
      (fields (field (name "MF") "Shenzhen LED Color Optoelectronic Inc."))
      (libsource (lib "eagle-import") (part "SK6812"))
    )
    (comp (ref "D116")
      (value "SK6812")
      (footprint "eagle-import:LED_SK6812")
      (fields (field (name "MF") "Shenzhen LED Color Optoelectronic Inc."))
      (libsource (lib "eagle-import") (part "SK6812"))
    )
    (comp (ref "D117")
      (value "SK6812")
      (footprint "eagle-import:LED_SK6812")
      (fields (field (name "MF") "Shenzhen LED Color Optoelectronic Inc."))
      (libsource (lib "eagle-import") (part "SK6812"))
    )
    (comp (ref "D118")
      (value "SK6812")
      (footprint "eagle-import:LED_SK6812")
      (fields (field (name "MF") "Shenzhen LED Color Optoelectronic Inc."))
      (libsource (lib "eagle-import") (part "SK6812"))
    )
    (comp (ref "D119")
      (value "SK6812")
      (footprint "eagle-import:LED_SK6812")
      (fields (field (name "MF") "Shenzhen LED Color Optoelectronic Inc."))
      (libsource (lib "eagle-import") (part "SK6812"))
    )
    (comp (ref "D120")
      (value "SK6812")
      (footprint "eagle-import:LED_SK6812")
      (fields (field (name "MF") "Shenzhen LED Color Optoelectronic Inc."))
      (libsource (lib "eagle-import") (part "SK6812"))
    )
    (comp (ref "D121")
      (value "SK6812")
      (footprint "eagle-import:LED_SK6812")
      (fields (field (name "MF") "Shenzhen LED Color Optoelectronic Inc."))
      (libsource (lib "eagle-import") (part "SK6812"))
    )
    (comp (ref "P1")
      (value "S3B-PH-SM4-TB")
      (footprint "eagle-import:JST_S3B-PH-SM4-TB")
      (fields (field (name "MF") "JST"))
      (libsource (lib "eagle-import") (part "S3B-PH-SM4-TB"))
    )
  )
  (nets
    (net (code "1") (name "+5V") (class "Default")
      (node (ref "C1") (pin "1") (pinfunction "1_1") (pintype "passive"))
      (node (ref "C10") (pin "1") (pinfunction "1_1") (pintype "passive"))
      (node (ref "C100") (pin "1") (pinfunction "1_1") (pintype "passive"))
      (node (ref "C101") (pin "1") (pinfunction "1_1") (pintype "passive"))
      (node (ref "C102") (pin "1") (pinfunction "1_1") (pintype "passive"))
      (node (ref "C103") (pin "1") (pinfunction "1_1") (pintype "passive"))
      (node (ref "C104") (pin "1") (pinfunction "1_1") (pintype "passive"))
      (node (ref "C105") (pin "1") (pinfunction "1_1") (pintype "passive"))
      (node (ref "C106") (pin "1") (pinfunction "1_1") (pintype "passive"))
      (node (ref "C107") (pin "1") (pinfunction "1_1") (pintype "passive"))
      (node (ref "C108") (pin "1") (pinfunction "1_1") (pintype "passive"))
      (node (ref "C109") (pin "1") (pinfunction "1_1") (pintype "passive"))
      (node (ref "C11") (pin "1") (pinfunction "1_1") (pintype "passive"))
      (node (ref "C110") (pin "1") (pinfunction "1_1") (pintype "passive"))
      (node (ref "C111") (pin "1") (pinfunction "1_1") (pintype "passive"))
      (node (ref "C112") (pin "1") (pinfunction "1_1") (pintype "passive"))
      (node (ref "C113") (pin "1") (pinfunction "1_1") (pintype "passive"))
      (node (ref "C114") (pin "1") (pinfunction "1_1") (pintype "passive"))
      (node (ref "C115") (pin "1") (pinfunction "1_1") (pintype "passive"))
      (node (ref "C116") (pin "1") (pinfunction "1_1") (pintype "passive"))
      (node (ref "C117") (pin "1") (pinfunction "1_1") (pintype "passive"))
      (node (ref "C118") (pin "1") (pinfunction "1_1") (pintype "passive"))
      (node (ref "C119") (pin "1") (pinfunction "1_1") (pintype "passive"))
      (node (ref "C12") (pin "1") (pinfunction "1_1") (pintype "passive"))
      (node (ref "C120") (pin "1") (pinfunction "1_1") (pintype "passive"))
      (node (ref "C121") (pin "1") (pinfunction "1_1") (pintype "passive"))
      (node (ref "C13") (pin "1") (pinfunction "1_1") (pintype "passive"))
      (node (ref "C14") (pin "1") (pinfunction "1_1") (pintype "passive"))
      (node (ref "C15") (pin "1") (pinfunction "1_1") (pintype "passive"))
      (node (ref "C16") (pin "1") (pinfunction "1_1") (pintype "passive"))
      (node (ref "C17") (pin "1") (pinfunction "1_1") (pintype "passive"))
      (node (ref "C18") (pin "1") (pinfunction "1_1") (pintype "passive"))
      (node (ref "C19") (pin "1") (pinfunction "1_1") (pintype "passive"))
      (node (ref "C2") (pin "1") (pinfunction "1_1") (pintype "passive"))
      (node (ref "C20") (pin "1") (pinfunction "1_1") (pintype "passive"))
      (node (ref "C21") (pin "1") (pinfunction "1_1") (pintype "passive"))
      (node (ref "C22") (pin "1") (pinfunction "1_1") (pintype "passive"))
      (node (ref "C23") (pin "1") (pinfunction "1_1") (pintype "passive"))
      (node (ref "C24") (pin "1") (pinfunction "1_1") (pintype "passive"))
      (node (ref "C25") (pin "1") (pinfunction "1_1") (pintype "passive"))
      (node (ref "C26") (pin "1") (pinfunction "1_1") (pintype "passive"))
      (node (ref "C27") (pin "1") (pinfunction "1_1") (pintype "passive"))
      (node (ref "C28") (pin "1") (pinfunction "1_1") (pintype "passive"))
      (node (ref "C29") (pin "1") (pinfunction "1_1") (pintype "passive"))
      (node (ref "C3") (pin "1") (pinfunction "1_1") (pintype "passive"))
      (node (ref "C30") (pin "1") (pinfunction "1_1") (pintype "passive"))
      (node (ref "C31") (pin "1") (pinfunction "1_1") (pintype "passive"))
      (node (ref "C32") (pin "1") (pinfunction "1_1") (pintype "passive"))
      (node (ref "C33") (pin "1") (pinfunction "1_1") (pintype "passive"))
      (node (ref "C34") (pin "1") (pinfunction "1_1") (pintype "passive"))
      (node (ref "C35") (pin "1") (pinfunction "1_1") (pintype "passive"))
      (node (ref "C36") (pin "1") (pinfunction "1_1") (pintype "passive"))
      (node (ref "C37") (pin "1") (pinfunction "1_1") (pintype "passive"))
      (node (ref "C38") (pin "1") (pinfunction "1_1") (pintype "passive"))
      (node (ref "C39") (pin "1") (pinfunction "1_1") (pintype "passive"))
      (node (ref "C4") (pin "1") (pinfunction "1_1") (pintype "passive"))
      (node (ref "C40") (pin "1") (pinfunction "1_1") (pintype "passive"))
      (node (ref "C41") (pin "1") (pinfunction "1_1") (pintype "passive"))
      (node (ref "C42") (pin "1") (pinfunction "1_1") (pintype "passive"))
      (node (ref "C43") (pin "1") (pinfunction "1_1") (pintype "passive"))
      (node (ref "C44") (pin "1") (pinfunction "1_1") (pintype "passive"))
      (node (ref "C45") (pin "1") (pinfunction "1_1") (pintype "passive"))
      (node (ref "C46") (pin "1") (pinfunction "1_1") (pintype "passive"))
      (node (ref "C47") (pin "1") (pinfunction "1_1") (pintype "passive"))
      (node (ref "C48") (pin "1") (pinfunction "1_1") (pintype "passive"))
      (node (ref "C49") (pin "1") (pinfunction "1_1") (pintype "passive"))
      (node (ref "C5") (pin "1") (pinfunction "1_1") (pintype "passive"))
      (node (ref "C50") (pin "1") (pinfunction "1_1") (pintype "passive"))
      (node (ref "C51") (pin "1") (pinfunction "1_1") (pintype "passive"))
      (node (ref "C52") (pin "1") (pinfunction "1_1") (pintype "passive"))
      (node (ref "C53") (pin "1") (pinfunction "1_1") (pintype "passive"))
      (node (ref "C54") (pin "1") (pinfunction "1_1") (pintype "passive"))
      (node (ref "C55") (pin "1") (pinfunction "1_1") (pintype "passive"))
      (node (ref "C56") (pin "1") (pinfunction "1_1") (pintype "passive"))
      (node (ref "C57") (pin "1") (pinfunction "1_1") (pintype "passive"))
      (node (ref "C58") (pin "1") (pinfunction "1_1") (pintype "passive"))
      (node (ref "C59") (pin "1") (pinfunction "1_1") (pintype "passive"))
      (node (ref "C6") (pin "1") (pinfunction "1_1") (pintype "passive"))
      (node (ref "C60") (pin "1") (pinfunction "1_1") (pintype "passive"))
      (node (ref "C61") (pin "1") (pinfunction "1_1") (pintype "passive"))
      (node (ref "C62") (pin "1") (pinfunction "1_1") (pintype "passive"))
      (node (ref "C63") (pin "1") (pinfunction "1_1") (pintype "passive"))
      (node (ref "C64") (pin "1") (pinfunction "1_1") (pintype "passive"))
      (node (ref "C65") (pin "1") (pinfunction "1_1") (pintype "passive"))
      (node (ref "C66") (pin "1") (pinfunction "1_1") (pintype "passive"))
      (node (ref "C67") (pin "1") (pinfunction "1_1") (pintype "passive"))
      (node (ref "C68") (pin "1") (pinfunction "1_1") (pintype "passive"))
      (node (ref "C69") (pin "1") (pinfunction "1_1") (pintype "passive"))
      (node (ref "C7") (pin "1") (pinfunction "1_1") (pintype "passive"))
      (node (ref "C70") (pin "1") (pinfunction "1_1") (pintype "passive"))
      (node (ref "C71") (pin "1") (pinfunction "1_1") (pintype "passive"))
      (node (ref "C72") (pin "1") (pinfunction "1_1") (pintype "passive"))
      (node (ref "C73") (pin "1") (pinfunction "1_1") (pintype "passive"))
      (node (ref "C74") (pin "1") (pinfunction "1_1") (pintype "passive"))
      (node (ref "C75") (pin "1") (pinfunction "1_1") (pintype "passive"))
      (node (ref "C76") (pin "1") (pinfunction "1_1") (pintype "passive"))
      (node (ref "C77") (pin "1") (pinfunction "1_1") (pintype "passive"))
      (node (ref "C78") (pin "1") (pinfunction "1_1") (pintype "passive"))
      (node (ref "C79") (pin "1") (pinfunction "1_1") (pintype "passive"))
      (node (ref "C8") (pin "1") (pinfunction "1_1") (pintype "passive"))
      (node (ref "C80") (pin "1") (pinfunction "1_1") (pintype "passive"))
      (node (ref "C81") (pin "1") (pinfunction "1_1") (pintype "passive"))
      (node (ref "C82") (pin "1") (pinfunction "1_1") (pintype "passive"))
      (node (ref "C83") (pin "1") (pinfunction "1_1") (pintype "passive"))
      (node (ref "C84") (pin "1") (pinfunction "1_1") (pintype "passive"))
      (node (ref "C85") (pin "1") (pinfunction "1_1") (pintype "passive"))
      (node (ref "C86") (pin "1") (pinfunction "1_1") (pintype "passive"))
      (node (ref "C87") (pin "1") (pinfunction "1_1") (pintype "passive"))
      (node (ref "C88") (pin "1") (pinfunction "1_1") (pintype "passive"))
      (node (ref "C89") (pin "1") (pinfunction "1_1") (pintype "passive"))
      (node (ref "C9") (pin "1") (pinfunction "1_1") (pintype "passive"))
      (node (ref "C90") (pin "1") (pinfunction "1_1") (pintype "passive"))
      (node (ref "C91") (pin "1") (pinfunction "1_1") (pintype "passive"))
      (node (ref "C92") (pin "1") (pinfunction "1_1") (pintype "passive"))
      (node (ref "C93") (pin "1") (pinfunction "1_1") (pintype "passive"))
      (node (ref "C94") (pin "1") (pinfunction "1_1") (pintype "passive"))
      (node (ref "C95") (pin "1") (pinfunction "1_1") (pintype "passive"))
      (node (ref "C96") (pin "1") (pinfunction "1_1") (pintype "passive"))
      (node (ref "C97") (pin "1") (pinfunction "1_1") (pintype "passive"))
      (node (ref "C98") (pin "1") (pinfunction "1_1") (pintype "passive"))
      (node (ref "C99") (pin "1") (pinfunction "1_1") (pintype "passive"))
      (node (ref "D1") (pin "1") (pinfunction "VDD_1") (pintype "power_in"))
      (node (ref "D10") (pin "1") (pinfunction "VDD_1") (pintype "power_in"))
      (node (ref "D100") (pin "1") (pinfunction "VDD_1") (pintype "power_in"))
      (node (ref "D101") (pin "1") (pinfunction "VDD_1") (pintype "power_in"))
      (node (ref "D102") (pin "1") (pinfunction "VDD_1") (pintype "power_in"))
      (node (ref "D103") (pin "1") (pinfunction "VDD_1") (pintype "power_in"))
      (node (ref "D104") (pin "1") (pinfunction "VDD_1") (pintype "power_in"))
      (node (ref "D105") (pin "1") (pinfunction "VDD_1") (pintype "power_in"))
      (node (ref "D106") (pin "1") (pinfunction "VDD_1") (pintype "power_in"))
      (node (ref "D107") (pin "1") (pinfunction "VDD_1") (pintype "power_in"))
      (node (ref "D108") (pin "1") (pinfunction "VDD_1") (pintype "power_in"))
      (node (ref "D109") (pin "1") (pinfunction "VDD_1") (pintype "power_in"))
      (node (ref "D11") (pin "1") (pinfunction "VDD_1") (pintype "power_in"))
      (node (ref "D110") (pin "1") (pinfunction "VDD_1") (pintype "power_in"))
      (node (ref "D111") (pin "1") (pinfunction "VDD_1") (pintype "power_in"))
      (node (ref "D112") (pin "1") (pinfunction "VDD_1") (pintype "power_in"))
      (node (ref "D113") (pin "1") (pinfunction "VDD_1") (pintype "power_in"))
      (node (ref "D114") (pin "1") (pinfunction "VDD_1") (pintype "power_in"))
      (node (ref "D115") (pin "1") (pinfunction "VDD_1") (pintype "power_in"))
      (node (ref "D116") (pin "1") (pinfunction "VDD_1") (pintype "power_in"))
      (node (ref "D117") (pin "1") (pinfunction "VDD_1") (pintype "power_in"))
      (node (ref "D118") (pin "1") (pinfunction "VDD_1") (pintype "power_in"))
      (node (ref "D119") (pin "1") (pinfunction "VDD_1") (pintype "power_in"))
      (node (ref "D12") (pin "1") (pinfunction "VDD_1") (pintype "power_in"))
      (node (ref "D120") (pin "1") (pinfunction "VDD_1") (pintype "power_in"))
      (node (ref "D121") (pin "1") (pinfunction "VDD_1") (pintype "power_in"))
      (node (ref "D13") (pin "1") (pinfunction "VDD_1") (pintype "power_in"))
      (node (ref "D14") (pin "1") (pinfunction "VDD_1") (pintype "power_in"))
      (node (ref "D15") (pin "1") (pinfunction "VDD_1") (pintype "power_in"))
      (node (ref "D16") (pin "1") (pinfunction "VDD_1") (pintype "power_in"))
      (node (ref "D17") (pin "1") (pinfunction "VDD_1") (pintype "power_in"))
      (node (ref "D18") (pin "1") (pinfunction "VDD_1") (pintype "power_in"))
      (node (ref "D19") (pin "1") (pinfunction "VDD_1") (pintype "power_in"))
      (node (ref "D2") (pin "1") (pinfunction "VDD_1") (pintype "power_in"))
      (node (ref "D20") (pin "1") (pinfunction "VDD_1") (pintype "power_in"))
      (node (ref "D21") (pin "1") (pinfunction "VDD_1") (pintype "power_in"))
      (node (ref "D22") (pin "1") (pinfunction "VDD_1") (pintype "power_in"))
      (node (ref "D23") (pin "1") (pinfunction "VDD_1") (pintype "power_in"))
      (node (ref "D24") (pin "1") (pinfunction "VDD_1") (pintype "power_in"))
      (node (ref "D25") (pin "1") (pinfunction "VDD_1") (pintype "power_in"))
      (node (ref "D26") (pin "1") (pinfunction "VDD_1") (pintype "power_in"))
      (node (ref "D27") (pin "1") (pinfunction "VDD_1") (pintype "power_in"))
      (node (ref "D28") (pin "1") (pinfunction "VDD_1") (pintype "power_in"))
      (node (ref "D29") (pin "1") (pinfunction "VDD_1") (pintype "power_in"))
      (node (ref "D3") (pin "1") (pinfunction "VDD_1") (pintype "power_in"))
      (node (ref "D30") (pin "1") (pinfunction "VDD_1") (pintype "power_in"))
      (node (ref "D31") (pin "1") (pinfunction "VDD_1") (pintype "power_in"))
      (node (ref "D32") (pin "1") (pinfunction "VDD_1") (pintype "power_in"))
      (node (ref "D33") (pin "1") (pinfunction "VDD_1") (pintype "power_in"))
      (node (ref "D34") (pin "1") (pinfunction "VDD_1") (pintype "power_in"))
      (node (ref "D35") (pin "1") (pinfunction "VDD_1") (pintype "power_in"))
      (node (ref "D36") (pin "1") (pinfunction "VDD_1") (pintype "power_in"))
      (node (ref "D37") (pin "1") (pinfunction "VDD_1") (pintype "power_in"))
      (node (ref "D38") (pin "1") (pinfunction "VDD_1") (pintype "power_in"))
      (node (ref "D39") (pin "1") (pinfunction "VDD_1") (pintype "power_in"))
      (node (ref "D4") (pin "1") (pinfunction "VDD_1") (pintype "power_in"))
      (node (ref "D40") (pin "1") (pinfunction "VDD_1") (pintype "power_in"))
      (node (ref "D41") (pin "1") (pinfunction "VDD_1") (pintype "power_in"))
      (node (ref "D42") (pin "1") (pinfunction "VDD_1") (pintype "power_in"))
      (node (ref "D43") (pin "1") (pinfunction "VDD_1") (pintype "power_in"))
      (node (ref "D44") (pin "1") (pinfunction "VDD_1") (pintype "power_in"))
      (node (ref "D45") (pin "1") (pinfunction "VDD_1") (pintype "power_in"))
      (node (ref "D46") (pin "1") (pinfunction "VDD_1") (pintype "power_in"))
      (node (ref "D47") (pin "1") (pinfunction "VDD_1") (pintype "power_in"))
      (node (ref "D48") (pin "1") (pinfunction "VDD_1") (pintype "power_in"))
      (node (ref "D49") (pin "1") (pinfunction "VDD_1") (pintype "power_in"))
      (node (ref "D5") (pin "1") (pinfunction "VDD_1") (pintype "power_in"))
      (node (ref "D50") (pin "1") (pinfunction "VDD_1") (pintype "power_in"))
      (node (ref "D51") (pin "1") (pinfunction "VDD_1") (pintype "power_in"))
      (node (ref "D52") (pin "1") (pinfunction "VDD_1") (pintype "power_in"))
      (node (ref "D53") (pin "1") (pinfunction "VDD_1") (pintype "power_in"))
      (node (ref "D54") (pin "1") (pinfunction "VDD_1") (pintype "power_in"))
      (node (ref "D55") (pin "1") (pinfunction "VDD_1") (pintype "power_in"))
      (node (ref "D56") (pin "1") (pinfunction "VDD_1") (pintype "power_in"))
      (node (ref "D57") (pin "1") (pinfunction "VDD_1") (pintype "power_in"))
      (node (ref "D58") (pin "1") (pinfunction "VDD_1") (pintype "power_in"))
      (node (ref "D59") (pin "1") (pinfunction "VDD_1") (pintype "power_in"))
      (node (ref "D6") (pin "1") (pinfunction "VDD_1") (pintype "power_in"))
      (node (ref "D60") (pin "1") (pinfunction "VDD_1") (pintype "power_in"))
      (node (ref "D61") (pin "1") (pinfunction "VDD_1") (pintype "power_in"))
      (node (ref "D62") (pin "1") (pinfunction "VDD_1") (pintype "power_in"))
      (node (ref "D63") (pin "1") (pinfunction "VDD_1") (pintype "power_in"))
      (node (ref "D64") (pin "1") (pinfunction "VDD_1") (pintype "power_in"))
      (node (ref "D65") (pin "1") (pinfunction "VDD_1") (pintype "power_in"))
      (node (ref "D66") (pin "1") (pinfunction "VDD_1") (pintype "power_in"))
      (node (ref "D67") (pin "1") (pinfunction "VDD_1") (pintype "power_in"))
      (node (ref "D68") (pin "1") (pinfunction "VDD_1") (pintype "power_in"))
      (node (ref "D69") (pin "1") (pinfunction "VDD_1") (pintype "power_in"))
      (node (ref "D7") (pin "1") (pinfunction "VDD_1") (pintype "power_in"))
      (node (ref "D70") (pin "1") (pinfunction "VDD_1") (pintype "power_in"))
      (node (ref "D71") (pin "1") (pinfunction "VDD_1") (pintype "power_in"))
      (node (ref "D72") (pin "1") (pinfunction "VDD_1") (pintype "power_in"))
      (node (ref "D73") (pin "1") (pinfunction "VDD_1") (pintype "power_in"))
      (node (ref "D74") (pin "1") (pinfunction "VDD_1") (pintype "power_in"))
      (node (ref "D75") (pin "1") (pinfunction "VDD_1") (pintype "power_in"))
      (node (ref "D76") (pin "1") (pinfunction "VDD_1") (pintype "power_in"))
      (node (ref "D77") (pin "1") (pinfunction "VDD_1") (pintype "power_in"))
      (node (ref "D78") (pin "1") (pinfunction "VDD_1") (pintype "power_in"))
      (node (ref "D79") (pin "1") (pinfunction "VDD_1") (pintype "power_in"))
      (node (ref "D8") (pin "1") (pinfunction "VDD_1") (pintype "power_in"))
      (node (ref "D80") (pin "1") (pinfunction "VDD_1") (pintype "power_in"))
      (node (ref "D81") (pin "1") (pinfunction "VDD_1") (pintype "power_in"))
      (node (ref "D82") (pin "1") (pinfunction "VDD_1") (pintype "power_in"))
      (node (ref "D83") (pin "1") (pinfunction "VDD_1") (pintype "power_in"))
      (node (ref "D84") (pin "1") (pinfunction "VDD_1") (pintype "power_in"))
      (node (ref "D85") (pin "1") (pinfunction "VDD_1") (pintype "power_in"))
      (node (ref "D86") (pin "1") (pinfunction "VDD_1") (pintype "power_in"))
      (node (ref "D87") (pin "1") (pinfunction "VDD_1") (pintype "power_in"))
      (node (ref "D88") (pin "1") (pinfunction "VDD_1") (pintype "power_in"))
      (node (ref "D89") (pin "1") (pinfunction "VDD_1") (pintype "power_in"))
      (node (ref "D9") (pin "1") (pinfunction "VDD_1") (pintype "power_in"))
      (node (ref "D90") (pin "1") (pinfunction "VDD_1") (pintype "power_in"))
      (node (ref "D91") (pin "1") (pinfunction "VDD_1") (pintype "power_in"))
      (node (ref "D92") (pin "1") (pinfunction "VDD_1") (pintype "power_in"))
      (node (ref "D93") (pin "1") (pinfunction "VDD_1") (pintype "power_in"))
      (node (ref "D94") (pin "1") (pinfunction "VDD_1") (pintype "power_in"))
      (node (ref "D95") (pin "1") (pinfunction "VDD_1") (pintype "power_in"))
      (node (ref "D96") (pin "1") (pinfunction "VDD_1") (pintype "power_in"))
      (node (ref "D97") (pin "1") (pinfunction "VDD_1") (pintype "power_in"))
      (node (ref "D98") (pin "1") (pinfunction "VDD_1") (pintype "power_in"))
      (node (ref "D99") (pin "1") (pinfunction "VDD_1") (pintype "power_in"))
      (node (ref "P1") (pin "1") (pinfunction "1_1") (pintype "passive"))
    )
    (net (code "2") (name "GND") (class "Default")
      (node (ref "C1") (pin "2") (pinfunction "2_2") (pintype "passive"))
      (node (ref "C10") (pin "2") (pinfunction "2_2") (pintype "passive"))
      (node (ref "C100") (pin "2") (pinfunction "2_2") (pintype "passive"))
      (node (ref "C101") (pin "2") (pinfunction "2_2") (pintype "passive"))
      (node (ref "C102") (pin "2") (pinfunction "2_2") (pintype "passive"))
      (node (ref "C103") (pin "2") (pinfunction "2_2") (pintype "passive"))
      (node (ref "C104") (pin "2") (pinfunction "2_2") (pintype "passive"))
      (node (ref "C105") (pin "2") (pinfunction "2_2") (pintype "passive"))
      (node (ref "C106") (pin "2") (pinfunction "2_2") (pintype "passive"))
      (node (ref "C107") (pin "2") (pinfunction "2_2") (pintype "passive"))
      (node (ref "C108") (pin "2") (pinfunction "2_2") (pintype "passive"))
      (node (ref "C109") (pin "2") (pinfunction "2_2") (pintype "passive"))
      (node (ref "C11") (pin "2") (pinfunction "2_2") (pintype "passive"))
      (node (ref "C110") (pin "2") (pinfunction "2_2") (pintype "passive"))
      (node (ref "C111") (pin "2") (pinfunction "2_2") (pintype "passive"))
      (node (ref "C112") (pin "2") (pinfunction "2_2") (pintype "passive"))
      (node (ref "C113") (pin "2") (pinfunction "2_2") (pintype "passive"))
      (node (ref "C114") (pin "2") (pinfunction "2_2") (pintype "passive"))
      (node (ref "C115") (pin "2") (pinfunction "2_2") (pintype "passive"))
      (node (ref "C116") (pin "2") (pinfunction "2_2") (pintype "passive"))
      (node (ref "C117") (pin "2") (pinfunction "2_2") (pintype "passive"))
      (node (ref "C118") (pin "2") (pinfunction "2_2") (pintype "passive"))
      (node (ref "C119") (pin "2") (pinfunction "2_2") (pintype "passive"))
      (node (ref "C12") (pin "2") (pinfunction "2_2") (pintype "passive"))
      (node (ref "C120") (pin "2") (pinfunction "2_2") (pintype "passive"))
      (node (ref "C121") (pin "2") (pinfunction "2_2") (pintype "passive"))
      (node (ref "C13") (pin "2") (pinfunction "2_2") (pintype "passive"))
      (node (ref "C14") (pin "2") (pinfunction "2_2") (pintype "passive"))
      (node (ref "C15") (pin "2") (pinfunction "2_2") (pintype "passive"))
      (node (ref "C16") (pin "2") (pinfunction "2_2") (pintype "passive"))
      (node (ref "C17") (pin "2") (pinfunction "2_2") (pintype "passive"))
      (node (ref "C18") (pin "2") (pinfunction "2_2") (pintype "passive"))
      (node (ref "C19") (pin "2") (pinfunction "2_2") (pintype "passive"))
      (node (ref "C2") (pin "2") (pinfunction "2_2") (pintype "passive"))
      (node (ref "C20") (pin "2") (pinfunction "2_2") (pintype "passive"))
      (node (ref "C21") (pin "2") (pinfunction "2_2") (pintype "passive"))
      (node (ref "C22") (pin "2") (pinfunction "2_2") (pintype "passive"))
      (node (ref "C23") (pin "2") (pinfunction "2_2") (pintype "passive"))
      (node (ref "C24") (pin "2") (pinfunction "2_2") (pintype "passive"))
      (node (ref "C25") (pin "2") (pinfunction "2_2") (pintype "passive"))
      (node (ref "C26") (pin "2") (pinfunction "2_2") (pintype "passive"))
      (node (ref "C27") (pin "2") (pinfunction "2_2") (pintype "passive"))
      (node (ref "C28") (pin "2") (pinfunction "2_2") (pintype "passive"))
      (node (ref "C29") (pin "2") (pinfunction "2_2") (pintype "passive"))
      (node (ref "C3") (pin "2") (pinfunction "2_2") (pintype "passive"))
      (node (ref "C30") (pin "2") (pinfunction "2_2") (pintype "passive"))
      (node (ref "C31") (pin "2") (pinfunction "2_2") (pintype "passive"))
      (node (ref "C32") (pin "2") (pinfunction "2_2") (pintype "passive"))
      (node (ref "C33") (pin "2") (pinfunction "2_2") (pintype "passive"))
      (node (ref "C34") (pin "2") (pinfunction "2_2") (pintype "passive"))
      (node (ref "C35") (pin "2") (pinfunction "2_2") (pintype "passive"))
      (node (ref "C36") (pin "2") (pinfunction "2_2") (pintype "passive"))
      (node (ref "C37") (pin "2") (pinfunction "2_2") (pintype "passive"))
      (node (ref "C38") (pin "2") (pinfunction "2_2") (pintype "passive"))
      (node (ref "C39") (pin "2") (pinfunction "2_2") (pintype "passive"))
      (node (ref "C4") (pin "2") (pinfunction "2_2") (pintype "passive"))
      (node (ref "C40") (pin "2") (pinfunction "2_2") (pintype "passive"))
      (node (ref "C41") (pin "2") (pinfunction "2_2") (pintype "passive"))
      (node (ref "C42") (pin "2") (pinfunction "2_2") (pintype "passive"))
      (node (ref "C43") (pin "2") (pinfunction "2_2") (pintype "passive"))
      (node (ref "C44") (pin "2") (pinfunction "2_2") (pintype "passive"))
      (node (ref "C45") (pin "2") (pinfunction "2_2") (pintype "passive"))
      (node (ref "C46") (pin "2") (pinfunction "2_2") (pintype "passive"))
      (node (ref "C47") (pin "2") (pinfunction "2_2") (pintype "passive"))
      (node (ref "C48") (pin "2") (pinfunction "2_2") (pintype "passive"))
      (node (ref "C49") (pin "2") (pinfunction "2_2") (pintype "passive"))
      (node (ref "C5") (pin "2") (pinfunction "2_2") (pintype "passive"))
      (node (ref "C50") (pin "2") (pinfunction "2_2") (pintype "passive"))
      (node (ref "C51") (pin "2") (pinfunction "2_2") (pintype "passive"))
      (node (ref "C52") (pin "2") (pinfunction "2_2") (pintype "passive"))
      (node (ref "C53") (pin "2") (pinfunction "2_2") (pintype "passive"))
      (node (ref "C54") (pin "2") (pinfunction "2_2") (pintype "passive"))
      (node (ref "C55") (pin "2") (pinfunction "2_2") (pintype "passive"))
      (node (ref "C56") (pin "2") (pinfunction "2_2") (pintype "passive"))
      (node (ref "C57") (pin "2") (pinfunction "2_2") (pintype "passive"))
      (node (ref "C58") (pin "2") (pinfunction "2_2") (pintype "passive"))
      (node (ref "C59") (pin "2") (pinfunction "2_2") (pintype "passive"))
      (node (ref "C6") (pin "2") (pinfunction "2_2") (pintype "passive"))
      (node (ref "C60") (pin "2") (pinfunction "2_2") (pintype "passive"))
      (node (ref "C61") (pin "2") (pinfunction "2_2") (pintype "passive"))
      (node (ref "C62") (pin "2") (pinfunction "2_2") (pintype "passive"))
      (node (ref "C63") (pin "2") (pinfunction "2_2") (pintype "passive"))
      (node (ref "C64") (pin "2") (pinfunction "2_2") (pintype "passive"))
      (node (ref "C65") (pin "2") (pinfunction "2_2") (pintype "passive"))
      (node (ref "C66") (pin "2") (pinfunction "2_2") (pintype "passive"))
      (node (ref "C67") (pin "2") (pinfunction "2_2") (pintype "passive"))
      (node (ref "C68") (pin "2") (pinfunction "2_2") (pintype "passive"))
      (node (ref "C69") (pin "2") (pinfunction "2_2") (pintype "passive"))
      (node (ref "C7") (pin "2") (pinfunction "2_2") (pintype "passive"))
      (node (ref "C70") (pin "2") (pinfunction "2_2") (pintype "passive"))
      (node (ref "C71") (pin "2") (pinfunction "2_2") (pintype "passive"))
      (node (ref "C72") (pin "2") (pinfunction "2_2") (pintype "passive"))
      (node (ref "C73") (pin "2") (pinfunction "2_2") (pintype "passive"))
      (node (ref "C74") (pin "2") (pinfunction "2_2") (pintype "passive"))
      (node (ref "C75") (pin "2") (pinfunction "2_2") (pintype "passive"))
      (node (ref "C76") (pin "2") (pinfunction "2_2") (pintype "passive"))
      (node (ref "C77") (pin "2") (pinfunction "2_2") (pintype "passive"))
      (node (ref "C78") (pin "2") (pinfunction "2_2") (pintype "passive"))
      (node (ref "C79") (pin "2") (pinfunction "2_2") (pintype "passive"))
      (node (ref "C8") (pin "2") (pinfunction "2_2") (pintype "passive"))
      (node (ref "C80") (pin "2") (pinfunction "2_2") (pintype "passive"))
      (node (ref "C81") (pin "2") (pinfunction "2_2") (pintype "passive"))
      (node (ref "C82") (pin "2") (pinfunction "2_2") (pintype "passive"))
      (node (ref "C83") (pin "2") (pinfunction "2_2") (pintype "passive"))
      (node (ref "C84") (pin "2") (pinfunction "2_2") (pintype "passive"))
      (node (ref "C85") (pin "2") (pinfunction "2_2") (pintype "passive"))
      (node (ref "C86") (pin "2") (pinfunction "2_2") (pintype "passive"))
      (node (ref "C87") (pin "2") (pinfunction "2_2") (pintype "passive"))
      (node (ref "C88") (pin "2") (pinfunction "2_2") (pintype "passive"))
      (node (ref "C89") (pin "2") (pinfunction "2_2") (pintype "passive"))
      (node (ref "C9") (pin "2") (pinfunction "2_2") (pintype "passive"))
      (node (ref "C90") (pin "2") (pinfunction "2_2") (pintype "passive"))
      (node (ref "C91") (pin "2") (pinfunction "2_2") (pintype "passive"))
      (node (ref "C92") (pin "2") (pinfunction "2_2") (pintype "passive"))
      (node (ref "C93") (pin "2") (pinfunction "2_2") (pintype "passive"))
      (node (ref "C94") (pin "2") (pinfunction "2_2") (pintype "passive"))
      (node (ref "C95") (pin "2") (pinfunction "2_2") (pintype "passive"))
      (node (ref "C96") (pin "2") (pinfunction "2_2") (pintype "passive"))
      (node (ref "C97") (pin "2") (pinfunction "2_2") (pintype "passive"))
      (node (ref "C98") (pin "2") (pinfunction "2_2") (pintype "passive"))
      (node (ref "C99") (pin "2") (pinfunction "2_2") (pintype "passive"))
      (node (ref "D1") (pin "3") (pinfunction "VSS_3") (pintype "power_in"))
      (node (ref "D10") (pin "3") (pinfunction "VSS_3") (pintype "power_in"))
      (node (ref "D100") (pin "3") (pinfunction "VSS_3") (pintype "power_in"))
      (node (ref "D101") (pin "3") (pinfunction "VSS_3") (pintype "power_in"))
      (node (ref "D102") (pin "3") (pinfunction "VSS_3") (pintype "power_in"))
      (node (ref "D103") (pin "3") (pinfunction "VSS_3") (pintype "power_in"))
      (node (ref "D104") (pin "3") (pinfunction "VSS_3") (pintype "power_in"))
      (node (ref "D105") (pin "3") (pinfunction "VSS_3") (pintype "power_in"))
      (node (ref "D106") (pin "3") (pinfunction "VSS_3") (pintype "power_in"))
      (node (ref "D107") (pin "3") (pinfunction "VSS_3") (pintype "power_in"))
      (node (ref "D108") (pin "3") (pinfunction "VSS_3") (pintype "power_in"))
      (node (ref "D109") (pin "3") (pinfunction "VSS_3") (pintype "power_in"))
      (node (ref "D11") (pin "3") (pinfunction "VSS_3") (pintype "power_in"))
      (node (ref "D110") (pin "3") (pinfunction "VSS_3") (pintype "power_in"))
      (node (ref "D111") (pin "3") (pinfunction "VSS_3") (pintype "power_in"))
      (node (ref "D112") (pin "3") (pinfunction "VSS_3") (pintype "power_in"))
      (node (ref "D113") (pin "3") (pinfunction "VSS_3") (pintype "power_in"))
      (node (ref "D114") (pin "3") (pinfunction "VSS_3") (pintype "power_in"))
      (node (ref "D115") (pin "3") (pinfunction "VSS_3") (pintype "power_in"))
      (node (ref "D116") (pin "3") (pinfunction "VSS_3") (pintype "power_in"))
      (node (ref "D117") (pin "3") (pinfunction "VSS_3") (pintype "power_in"))
      (node (ref "D118") (pin "3") (pinfunction "VSS_3") (pintype "power_in"))
      (node (ref "D119") (pin "3") (pinfunction "VSS_3") (pintype "power_in"))
      (node (ref "D12") (pin "3") (pinfunction "VSS_3") (pintype "power_in"))
      (node (ref "D120") (pin "3") (pinfunction "VSS_3") (pintype "power_in"))
      (node (ref "D121") (pin "3") (pinfunction "VSS_3") (pintype "power_in"))
      (node (ref "D13") (pin "3") (pinfunction "VSS_3") (pintype "power_in"))
      (node (ref "D14") (pin "3") (pinfunction "VSS_3") (pintype "power_in"))
      (node (ref "D15") (pin "3") (pinfunction "VSS_3") (pintype "power_in"))
      (node (ref "D16") (pin "3") (pinfunction "VSS_3") (pintype "power_in"))
      (node (ref "D17") (pin "3") (pinfunction "VSS_3") (pintype "power_in"))
      (node (ref "D18") (pin "3") (pinfunction "VSS_3") (pintype "power_in"))
      (node (ref "D19") (pin "3") (pinfunction "VSS_3") (pintype "power_in"))
      (node (ref "D2") (pin "3") (pinfunction "VSS_3") (pintype "power_in"))
      (node (ref "D20") (pin "3") (pinfunction "VSS_3") (pintype "power_in"))
      (node (ref "D21") (pin "3") (pinfunction "VSS_3") (pintype "power_in"))
      (node (ref "D22") (pin "3") (pinfunction "VSS_3") (pintype "power_in"))
      (node (ref "D23") (pin "3") (pinfunction "VSS_3") (pintype "power_in"))
      (node (ref "D24") (pin "3") (pinfunction "VSS_3") (pintype "power_in"))
      (node (ref "D25") (pin "3") (pinfunction "VSS_3") (pintype "power_in"))
      (node (ref "D26") (pin "3") (pinfunction "VSS_3") (pintype "power_in"))
      (node (ref "D27") (pin "3") (pinfunction "VSS_3") (pintype "power_in"))
      (node (ref "D28") (pin "3") (pinfunction "VSS_3") (pintype "power_in"))
      (node (ref "D29") (pin "3") (pinfunction "VSS_3") (pintype "power_in"))
      (node (ref "D3") (pin "3") (pinfunction "VSS_3") (pintype "power_in"))
      (node (ref "D30") (pin "3") (pinfunction "VSS_3") (pintype "power_in"))
      (node (ref "D31") (pin "3") (pinfunction "VSS_3") (pintype "power_in"))
      (node (ref "D32") (pin "3") (pinfunction "VSS_3") (pintype "power_in"))
      (node (ref "D33") (pin "3") (pinfunction "VSS_3") (pintype "power_in"))
      (node (ref "D34") (pin "3") (pinfunction "VSS_3") (pintype "power_in"))
      (node (ref "D35") (pin "3") (pinfunction "VSS_3") (pintype "power_in"))
      (node (ref "D36") (pin "3") (pinfunction "VSS_3") (pintype "power_in"))
      (node (ref "D37") (pin "3") (pinfunction "VSS_3") (pintype "power_in"))
      (node (ref "D38") (pin "3") (pinfunction "VSS_3") (pintype "power_in"))
      (node (ref "D39") (pin "3") (pinfunction "VSS_3") (pintype "power_in"))
      (node (ref "D4") (pin "3") (pinfunction "VSS_3") (pintype "power_in"))
      (node (ref "D40") (pin "3") (pinfunction "VSS_3") (pintype "power_in"))
      (node (ref "D41") (pin "3") (pinfunction "VSS_3") (pintype "power_in"))
      (node (ref "D42") (pin "3") (pinfunction "VSS_3") (pintype "power_in"))
      (node (ref "D43") (pin "3") (pinfunction "VSS_3") (pintype "power_in"))
      (node (ref "D44") (pin "3") (pinfunction "VSS_3") (pintype "power_in"))
      (node (ref "D45") (pin "3") (pinfunction "VSS_3") (pintype "power_in"))
      (node (ref "D46") (pin "3") (pinfunction "VSS_3") (pintype "power_in"))
      (node (ref "D47") (pin "3") (pinfunction "VSS_3") (pintype "power_in"))
      (node (ref "D48") (pin "3") (pinfunction "VSS_3") (pintype "power_in"))
      (node (ref "D49") (pin "3") (pinfunction "VSS_3") (pintype "power_in"))
      (node (ref "D5") (pin "3") (pinfunction "VSS_3") (pintype "power_in"))
      (node (ref "D50") (pin "3") (pinfunction "VSS_3") (pintype "power_in"))
      (node (ref "D51") (pin "3") (pinfunction "VSS_3") (pintype "power_in"))
      (node (ref "D52") (pin "3") (pinfunction "VSS_3") (pintype "power_in"))
      (node (ref "D53") (pin "3") (pinfunction "VSS_3") (pintype "power_in"))
      (node (ref "D54") (pin "3") (pinfunction "VSS_3") (pintype "power_in"))
      (node (ref "D55") (pin "3") (pinfunction "VSS_3") (pintype "power_in"))
      (node (ref "D56") (pin "3") (pinfunction "VSS_3") (pintype "power_in"))
      (node (ref "D57") (pin "3") (pinfunction "VSS_3") (pintype "power_in"))
      (node (ref "D58") (pin "3") (pinfunction "VSS_3") (pintype "power_in"))
      (node (ref "D59") (pin "3") (pinfunction "VSS_3") (pintype "power_in"))
      (node (ref "D6") (pin "3") (pinfunction "VSS_3") (pintype "power_in"))
      (node (ref "D60") (pin "3") (pinfunction "VSS_3") (pintype "power_in"))
      (node (ref "D61") (pin "3") (pinfunction "VSS_3") (pintype "power_in"))
      (node (ref "D62") (pin "3") (pinfunction "VSS_3") (pintype "power_in"))
      (node (ref "D63") (pin "3") (pinfunction "VSS_3") (pintype "power_in"))
      (node (ref "D64") (pin "3") (pinfunction "VSS_3") (pintype "power_in"))
      (node (ref "D65") (pin "3") (pinfunction "VSS_3") (pintype "power_in"))
      (node (ref "D66") (pin "3") (pinfunction "VSS_3") (pintype "power_in"))
      (node (ref "D67") (pin "3") (pinfunction "VSS_3") (pintype "power_in"))
      (node (ref "D68") (pin "3") (pinfunction "VSS_3") (pintype "power_in"))
      (node (ref "D69") (pin "3") (pinfunction "VSS_3") (pintype "power_in"))
      (node (ref "D7") (pin "3") (pinfunction "VSS_3") (pintype "power_in"))
      (node (ref "D70") (pin "3") (pinfunction "VSS_3") (pintype "power_in"))
      (node (ref "D71") (pin "3") (pinfunction "VSS_3") (pintype "power_in"))
      (node (ref "D72") (pin "3") (pinfunction "VSS_3") (pintype "power_in"))
      (node (ref "D73") (pin "3") (pinfunction "VSS_3") (pintype "power_in"))
      (node (ref "D74") (pin "3") (pinfunction "VSS_3") (pintype "power_in"))
      (node (ref "D75") (pin "3") (pinfunction "VSS_3") (pintype "power_in"))
      (node (ref "D76") (pin "3") (pinfunction "VSS_3") (pintype "power_in"))
      (node (ref "D77") (pin "3") (pinfunction "VSS_3") (pintype "power_in"))
      (node (ref "D78") (pin "3") (pinfunction "VSS_3") (pintype "power_in"))
      (node (ref "D79") (pin "3") (pinfunction "VSS_3") (pintype "power_in"))
      (node (ref "D8") (pin "3") (pinfunction "VSS_3") (pintype "power_in"))
      (node (ref "D80") (pin "3") (pinfunction "VSS_3") (pintype "power_in"))
      (node (ref "D81") (pin "3") (pinfunction "VSS_3") (pintype "power_in"))
      (node (ref "D82") (pin "3") (pinfunction "VSS_3") (pintype "power_in"))
      (node (ref "D83") (pin "3") (pinfunction "VSS_3") (pintype "power_in"))
      (node (ref "D84") (pin "3") (pinfunction "VSS_3") (pintype "power_in"))
      (node (ref "D85") (pin "3") (pinfunction "VSS_3") (pintype "power_in"))
      (node (ref "D86") (pin "3") (pinfunction "VSS_3") (pintype "power_in"))
      (node (ref "D87") (pin "3") (pinfunction "VSS_3") (pintype "power_in"))
      (node (ref "D88") (pin "3") (pinfunction "VSS_3") (pintype "power_in"))
      (node (ref "D89") (pin "3") (pinfunction "VSS_3") (pintype "power_in"))
      (node (ref "D9") (pin "3") (pinfunction "VSS_3") (pintype "power_in"))
      (node (ref "D90") (pin "3") (pinfunction "VSS_3") (pintype "power_in"))
      (node (ref "D91") (pin "3") (pinfunction "VSS_3") (pintype "power_in"))
      (node (ref "D92") (pin "3") (pinfunction "VSS_3") (pintype "power_in"))
      (node (ref "D93") (pin "3") (pinfunction "VSS_3") (pintype "power_in"))
      (node (ref "D94") (pin "3") (pinfunction "VSS_3") (pintype "power_in"))
      (node (ref "D95") (pin "3") (pinfunction "VSS_3") (pintype "power_in"))
      (node (ref "D96") (pin "3") (pinfunction "VSS_3") (pintype "power_in"))
      (node (ref "D97") (pin "3") (pinfunction "VSS_3") (pintype "power_in"))
      (node (ref "D98") (pin "3") (pinfunction "VSS_3") (pintype "power_in"))
      (node (ref "D99") (pin "3") (pinfunction "VSS_3") (pintype "power_in"))
      (node (ref "P1") (pin "2") (pinfunction "2_2") (pintype "passive"))
    )
    (net (code "3") (name "Net-(D1-DOUT)") (class "Default")
      (node (ref "D1") (pin "2") (pinfunction "DOUT_2") (pintype "output"))
      (node (ref "D2") (pin "4") (pinfunction "DIN_4") (pintype "input"))
    )
    (net (code "4") (name "Net-(D2-DOUT)") (class "Default")
      (node (ref "D2") (pin "2") (pinfunction "DOUT_2") (pintype "output"))
      (node (ref "D3") (pin "4") (pinfunction "DIN_4") (pintype "input"))
    )
    (net (code "5") (name "Net-(D3-DOUT)") (class "Default")
      (node (ref "D3") (pin "2") (pinfunction "DOUT_2") (pintype "output"))
      (node (ref "D4") (pin "4") (pinfunction "DIN_4") (pintype "input"))
    )
    (net (code "6") (name "Net-(D4-DOUT)") (class "Default")
      (node (ref "D4") (pin "2") (pinfunction "DOUT_2") (pintype "output"))
      (node (ref "D5") (pin "4") (pinfunction "DIN_4") (pintype "input"))
    )
    (net (code "7") (name "Net-(D5-DOUT)") (class "Default")
      (node (ref "D5") (pin "2") (pinfunction "DOUT_2") (pintype "output"))
      (node (ref "D6") (pin "4") (pinfunction "DIN_4") (pintype "input"))
    )
    (net (code "8") (name "Net-(D6-DOUT)") (class "Default")
      (node (ref "D6") (pin "2") (pinfunction "DOUT_2") (pintype "output"))
      (node (ref "D7") (pin "4") (pinfunction "DIN_4") (pintype "input"))
    )
    (net (code "9") (name "Net-(D7-DOUT)") (class "Default")
      (node (ref "D7") (pin "2") (pinfunction "DOUT_2") (pintype "output"))
      (node (ref "D8") (pin "4") (pinfunction "DIN_4") (pintype "input"))
    )
    (net (code "10") (name "Net-(D8-DOUT)") (class "Default")
      (node (ref "D8") (pin "2") (pinfunction "DOUT_2") (pintype "output"))
      (node (ref "D9") (pin "4") (pinfunction "DIN_4") (pintype "input"))
    )
    (net (code "11") (name "Net-(D10-DIN)") (class "Default")
      (node (ref "D10") (pin "4") (pinfunction "DIN_4") (pintype "input"))
      (node (ref "D9") (pin "2") (pinfunction "DOUT_2") (pintype "output"))
    )
    (net (code "12") (name "Net-(D10-DOUT)") (class "Default")
      (node (ref "D10") (pin "2") (pinfunction "DOUT_2") (pintype "output"))
      (node (ref "D11") (pin "4") (pinfunction "DIN_4") (pintype "input"))
    )
    (net (code "13") (name "Net-(D12-DOUT)") (class "Default")
      (node (ref "D12") (pin "2") (pinfunction "DOUT_2") (pintype "output"))
      (node (ref "D13") (pin "4") (pinfunction "DIN_4") (pintype "input"))
    )
    (net (code "14") (name "Net-(D13-DOUT)") (class "Default")
      (node (ref "D13") (pin "2") (pinfunction "DOUT_2") (pintype "output"))
      (node (ref "D14") (pin "4") (pinfunction "DIN_4") (pintype "input"))
    )
    (net (code "15") (name "Net-(D14-DOUT)") (class "Default")
      (node (ref "D14") (pin "2") (pinfunction "DOUT_2") (pintype "output"))
      (node (ref "D15") (pin "4") (pinfunction "DIN_4") (pintype "input"))
    )
    (net (code "16") (name "Net-(D15-DOUT)") (class "Default")
      (node (ref "D15") (pin "2") (pinfunction "DOUT_2") (pintype "output"))
      (node (ref "D16") (pin "4") (pinfunction "DIN_4") (pintype "input"))
    )
    (net (code "17") (name "Net-(D16-DOUT)") (class "Default")
      (node (ref "D16") (pin "2") (pinfunction "DOUT_2") (pintype "output"))
      (node (ref "D17") (pin "4") (pinfunction "DIN_4") (pintype "input"))
    )
    (net (code "18") (name "Net-(D17-DOUT)") (class "Default")
      (node (ref "D17") (pin "2") (pinfunction "DOUT_2") (pintype "output"))
      (node (ref "D18") (pin "4") (pinfunction "DIN_4") (pintype "input"))
    )
    (net (code "19") (name "Net-(D18-DOUT)") (class "Default")
      (node (ref "D18") (pin "2") (pinfunction "DOUT_2") (pintype "output"))
      (node (ref "D19") (pin "4") (pinfunction "DIN_4") (pintype "input"))
    )
    (net (code "20") (name "Net-(D19-DOUT)") (class "Default")
      (node (ref "D19") (pin "2") (pinfunction "DOUT_2") (pintype "output"))
      (node (ref "D20") (pin "4") (pinfunction "DIN_4") (pintype "input"))
    )
    (net (code "21") (name "Net-(D20-DOUT)") (class "Default")
      (node (ref "D20") (pin "2") (pinfunction "DOUT_2") (pintype "output"))
      (node (ref "D21") (pin "4") (pinfunction "DIN_4") (pintype "input"))
    )
    (net (code "22") (name "Net-(D21-DOUT)") (class "Default")
      (node (ref "D21") (pin "2") (pinfunction "DOUT_2") (pintype "output"))
      (node (ref "D22") (pin "4") (pinfunction "DIN_4") (pintype "input"))
    )
    (net (code "23") (name "Net-(D23-DOUT)") (class "Default")
      (node (ref "D23") (pin "2") (pinfunction "DOUT_2") (pintype "output"))
      (node (ref "D24") (pin "4") (pinfunction "DIN_4") (pintype "input"))
    )
    (net (code "24") (name "Net-(D24-DOUT)") (class "Default")
      (node (ref "D24") (pin "2") (pinfunction "DOUT_2") (pintype "output"))
      (node (ref "D25") (pin "4") (pinfunction "DIN_4") (pintype "input"))
    )
    (net (code "25") (name "Net-(D25-DOUT)") (class "Default")
      (node (ref "D25") (pin "2") (pinfunction "DOUT_2") (pintype "output"))
      (node (ref "D26") (pin "4") (pinfunction "DIN_4") (pintype "input"))
    )
    (net (code "26") (name "Net-(D26-DOUT)") (class "Default")
      (node (ref "D26") (pin "2") (pinfunction "DOUT_2") (pintype "output"))
      (node (ref "D27") (pin "4") (pinfunction "DIN_4") (pintype "input"))
    )
    (net (code "27") (name "Net-(D27-DOUT)") (class "Default")
      (node (ref "D27") (pin "2") (pinfunction "DOUT_2") (pintype "output"))
      (node (ref "D28") (pin "4") (pinfunction "DIN_4") (pintype "input"))
    )
    (net (code "28") (name "Net-(D28-DOUT)") (class "Default")
      (node (ref "D28") (pin "2") (pinfunction "DOUT_2") (pintype "output"))
      (node (ref "D29") (pin "4") (pinfunction "DIN_4") (pintype "input"))
    )
    (net (code "29") (name "Net-(D29-DOUT)") (class "Default")
      (node (ref "D29") (pin "2") (pinfunction "DOUT_2") (pintype "output"))
      (node (ref "D30") (pin "4") (pinfunction "DIN_4") (pintype "input"))
    )
    (net (code "30") (name "Net-(D30-DOUT)") (class "Default")
      (node (ref "D30") (pin "2") (pinfunction "DOUT_2") (pintype "output"))
      (node (ref "D31") (pin "4") (pinfunction "DIN_4") (pintype "input"))
    )
    (net (code "31") (name "Net-(D31-DOUT)") (class "Default")
      (node (ref "D31") (pin "2") (pinfunction "DOUT_2") (pintype "output"))
      (node (ref "D32") (pin "4") (pinfunction "DIN_4") (pintype "input"))
    )
    (net (code "32") (name "Net-(D32-DOUT)") (class "Default")
      (node (ref "D32") (pin "2") (pinfunction "DOUT_2") (pintype "output"))
      (node (ref "D33") (pin "4") (pinfunction "DIN_4") (pintype "input"))
    )
    (net (code "33") (name "Net-(D34-DOUT)") (class "Default")
      (node (ref "D34") (pin "2") (pinfunction "DOUT_2") (pintype "output"))
      (node (ref "D35") (pin "4") (pinfunction "DIN_4") (pintype "input"))
    )
    (net (code "34") (name "Net-(D35-DOUT)") (class "Default")
      (node (ref "D35") (pin "2") (pinfunction "DOUT_2") (pintype "output"))
      (node (ref "D36") (pin "4") (pinfunction "DIN_4") (pintype "input"))
    )
    (net (code "35") (name "Net-(D36-DOUT)") (class "Default")
      (node (ref "D36") (pin "2") (pinfunction "DOUT_2") (pintype "output"))
      (node (ref "D37") (pin "4") (pinfunction "DIN_4") (pintype "input"))
    )
    (net (code "36") (name "Net-(D37-DOUT)") (class "Default")
      (node (ref "D37") (pin "2") (pinfunction "DOUT_2") (pintype "output"))
      (node (ref "D38") (pin "4") (pinfunction "DIN_4") (pintype "input"))
    )
    (net (code "37") (name "Net-(D38-DOUT)") (class "Default")
      (node (ref "D38") (pin "2") (pinfunction "DOUT_2") (pintype "output"))
      (node (ref "D39") (pin "4") (pinfunction "DIN_4") (pintype "input"))
    )
    (net (code "38") (name "Net-(D39-DOUT)") (class "Default")
      (node (ref "D39") (pin "2") (pinfunction "DOUT_2") (pintype "output"))
      (node (ref "D40") (pin "4") (pinfunction "DIN_4") (pintype "input"))
    )
    (net (code "39") (name "Net-(D40-DOUT)") (class "Default")
      (node (ref "D40") (pin "2") (pinfunction "DOUT_2") (pintype "output"))
      (node (ref "D41") (pin "4") (pinfunction "DIN_4") (pintype "input"))
    )
    (net (code "40") (name "Net-(D41-DOUT)") (class "Default")
      (node (ref "D41") (pin "2") (pinfunction "DOUT_2") (pintype "output"))
      (node (ref "D42") (pin "4") (pinfunction "DIN_4") (pintype "input"))
    )
    (net (code "41") (name "Net-(D42-DOUT)") (class "Default")
      (node (ref "D42") (pin "2") (pinfunction "DOUT_2") (pintype "output"))
      (node (ref "D43") (pin "4") (pinfunction "DIN_4") (pintype "input"))
    )
    (net (code "42") (name "Net-(D43-DOUT)") (class "Default")
      (node (ref "D43") (pin "2") (pinfunction "DOUT_2") (pintype "output"))
      (node (ref "D44") (pin "4") (pinfunction "DIN_4") (pintype "input"))
    )
    (net (code "43") (name "Net-(D45-DOUT)") (class "Default")
      (node (ref "D45") (pin "2") (pinfunction "DOUT_2") (pintype "output"))
      (node (ref "D46") (pin "4") (pinfunction "DIN_4") (pintype "input"))
    )
    (net (code "44") (name "Net-(D46-DOUT)") (class "Default")
      (node (ref "D46") (pin "2") (pinfunction "DOUT_2") (pintype "output"))
      (node (ref "D47") (pin "4") (pinfunction "DIN_4") (pintype "input"))
    )
    (net (code "45") (name "Net-(D47-DOUT)") (class "Default")
      (node (ref "D47") (pin "2") (pinfunction "DOUT_2") (pintype "output"))
      (node (ref "D48") (pin "4") (pinfunction "DIN_4") (pintype "input"))
    )
    (net (code "46") (name "Net-(D48-DOUT)") (class "Default")
      (node (ref "D48") (pin "2") (pinfunction "DOUT_2") (pintype "output"))
      (node (ref "D49") (pin "4") (pinfunction "DIN_4") (pintype "input"))
    )
    (net (code "47") (name "Net-(D49-DOUT)") (class "Default")
      (node (ref "D49") (pin "2") (pinfunction "DOUT_2") (pintype "output"))
      (node (ref "D50") (pin "4") (pinfunction "DIN_4") (pintype "input"))
    )
    (net (code "48") (name "Net-(D50-DOUT)") (class "Default")
      (node (ref "D50") (pin "2") (pinfunction "DOUT_2") (pintype "output"))
      (node (ref "D51") (pin "4") (pinfunction "DIN_4") (pintype "input"))
    )
    (net (code "49") (name "Net-(D51-DOUT)") (class "Default")
      (node (ref "D51") (pin "2") (pinfunction "DOUT_2") (pintype "output"))
      (node (ref "D52") (pin "4") (pinfunction "DIN_4") (pintype "input"))
    )
    (net (code "50") (name "Net-(D52-DOUT)") (class "Default")
      (node (ref "D52") (pin "2") (pinfunction "DOUT_2") (pintype "output"))
      (node (ref "D53") (pin "4") (pinfunction "DIN_4") (pintype "input"))
    )
    (net (code "51") (name "Net-(D53-DOUT)") (class "Default")
      (node (ref "D53") (pin "2") (pinfunction "DOUT_2") (pintype "output"))
      (node (ref "D54") (pin "4") (pinfunction "DIN_4") (pintype "input"))
    )
    (net (code "52") (name "Net-(D54-DOUT)") (class "Default")
      (node (ref "D54") (pin "2") (pinfunction "DOUT_2") (pintype "output"))
      (node (ref "D55") (pin "4") (pinfunction "DIN_4") (pintype "input"))
    )
    (net (code "53") (name "Net-(D56-DOUT)") (class "Default")
      (node (ref "D56") (pin "2") (pinfunction "DOUT_2") (pintype "output"))
      (node (ref "D57") (pin "4") (pinfunction "DIN_4") (pintype "input"))
    )
    (net (code "54") (name "Net-(D57-DOUT)") (class "Default")
      (node (ref "D57") (pin "2") (pinfunction "DOUT_2") (pintype "output"))
      (node (ref "D58") (pin "4") (pinfunction "DIN_4") (pintype "input"))
    )
    (net (code "55") (name "Net-(D58-DOUT)") (class "Default")
      (node (ref "D58") (pin "2") (pinfunction "DOUT_2") (pintype "output"))
      (node (ref "D59") (pin "4") (pinfunction "DIN_4") (pintype "input"))
    )
    (net (code "56") (name "Net-(D59-DOUT)") (class "Default")
      (node (ref "D59") (pin "2") (pinfunction "DOUT_2") (pintype "output"))
      (node (ref "D60") (pin "4") (pinfunction "DIN_4") (pintype "input"))
    )
    (net (code "57") (name "Net-(D60-DOUT)") (class "Default")
      (node (ref "D60") (pin "2") (pinfunction "DOUT_2") (pintype "output"))
      (node (ref "D61") (pin "4") (pinfunction "DIN_4") (pintype "input"))
    )
    (net (code "58") (name "Net-(D61-DOUT)") (class "Default")
      (node (ref "D61") (pin "2") (pinfunction "DOUT_2") (pintype "output"))
      (node (ref "D62") (pin "4") (pinfunction "DIN_4") (pintype "input"))
    )
    (net (code "59") (name "Net-(D62-DOUT)") (class "Default")
      (node (ref "D62") (pin "2") (pinfunction "DOUT_2") (pintype "output"))
      (node (ref "D63") (pin "4") (pinfunction "DIN_4") (pintype "input"))
    )
    (net (code "60") (name "Net-(D63-DOUT)") (class "Default")
      (node (ref "D63") (pin "2") (pinfunction "DOUT_2") (pintype "output"))
      (node (ref "D64") (pin "4") (pinfunction "DIN_4") (pintype "input"))
    )
    (net (code "61") (name "Net-(D64-DOUT)") (class "Default")
      (node (ref "D64") (pin "2") (pinfunction "DOUT_2") (pintype "output"))
      (node (ref "D65") (pin "4") (pinfunction "DIN_4") (pintype "input"))
    )
    (net (code "62") (name "Net-(D65-DOUT)") (class "Default")
      (node (ref "D65") (pin "2") (pinfunction "DOUT_2") (pintype "output"))
      (node (ref "D66") (pin "4") (pinfunction "DIN_4") (pintype "input"))
    )
    (net (code "63") (name "Net-(D67-DOUT)") (class "Default")
      (node (ref "D67") (pin "2") (pinfunction "DOUT_2") (pintype "output"))
      (node (ref "D68") (pin "4") (pinfunction "DIN_4") (pintype "input"))
    )
    (net (code "64") (name "Net-(D68-DOUT)") (class "Default")
      (node (ref "D68") (pin "2") (pinfunction "DOUT_2") (pintype "output"))
      (node (ref "D69") (pin "4") (pinfunction "DIN_4") (pintype "input"))
    )
    (net (code "65") (name "Net-(D69-DOUT)") (class "Default")
      (node (ref "D69") (pin "2") (pinfunction "DOUT_2") (pintype "output"))
      (node (ref "D70") (pin "4") (pinfunction "DIN_4") (pintype "input"))
    )
    (net (code "66") (name "Net-(D70-DOUT)") (class "Default")
      (node (ref "D70") (pin "2") (pinfunction "DOUT_2") (pintype "output"))
      (node (ref "D71") (pin "4") (pinfunction "DIN_4") (pintype "input"))
    )
    (net (code "67") (name "Net-(D71-DOUT)") (class "Default")
      (node (ref "D71") (pin "2") (pinfunction "DOUT_2") (pintype "output"))
      (node (ref "D72") (pin "4") (pinfunction "DIN_4") (pintype "input"))
    )
    (net (code "68") (name "Net-(D72-DOUT)") (class "Default")
      (node (ref "D72") (pin "2") (pinfunction "DOUT_2") (pintype "output"))
      (node (ref "D73") (pin "4") (pinfunction "DIN_4") (pintype "input"))
    )
    (net (code "69") (name "Net-(D73-DOUT)") (class "Default")
      (node (ref "D73") (pin "2") (pinfunction "DOUT_2") (pintype "output"))
      (node (ref "D74") (pin "4") (pinfunction "DIN_4") (pintype "input"))
    )
    (net (code "70") (name "Net-(D74-DOUT)") (class "Default")
      (node (ref "D74") (pin "2") (pinfunction "DOUT_2") (pintype "output"))
      (node (ref "D75") (pin "4") (pinfunction "DIN_4") (pintype "input"))
    )
    (net (code "71") (name "Net-(D75-DOUT)") (class "Default")
      (node (ref "D75") (pin "2") (pinfunction "DOUT_2") (pintype "output"))
      (node (ref "D76") (pin "4") (pinfunction "DIN_4") (pintype "input"))
    )
    (net (code "72") (name "Net-(D76-DOUT)") (class "Default")
      (node (ref "D76") (pin "2") (pinfunction "DOUT_2") (pintype "output"))
      (node (ref "D77") (pin "4") (pinfunction "DIN_4") (pintype "input"))
    )
    (net (code "73") (name "Net-(D78-DOUT)") (class "Default")
      (node (ref "D78") (pin "2") (pinfunction "DOUT_2") (pintype "output"))
      (node (ref "D79") (pin "4") (pinfunction "DIN_4") (pintype "input"))
    )
    (net (code "74") (name "Net-(D79-DOUT)") (class "Default")
      (node (ref "D79") (pin "2") (pinfunction "DOUT_2") (pintype "output"))
      (node (ref "D80") (pin "4") (pinfunction "DIN_4") (pintype "input"))
    )
    (net (code "75") (name "Net-(D80-DOUT)") (class "Default")
      (node (ref "D80") (pin "2") (pinfunction "DOUT_2") (pintype "output"))
      (node (ref "D81") (pin "4") (pinfunction "DIN_4") (pintype "input"))
    )
    (net (code "76") (name "Net-(D81-DOUT)") (class "Default")
      (node (ref "D81") (pin "2") (pinfunction "DOUT_2") (pintype "output"))
      (node (ref "D82") (pin "4") (pinfunction "DIN_4") (pintype "input"))
    )
    (net (code "77") (name "Net-(D82-DOUT)") (class "Default")
      (node (ref "D82") (pin "2") (pinfunction "DOUT_2") (pintype "output"))
      (node (ref "D83") (pin "4") (pinfunction "DIN_4") (pintype "input"))
    )
    (net (code "78") (name "Net-(D83-DOUT)") (class "Default")
      (node (ref "D83") (pin "2") (pinfunction "DOUT_2") (pintype "output"))
      (node (ref "D84") (pin "4") (pinfunction "DIN_4") (pintype "input"))
    )
    (net (code "79") (name "Net-(D84-DOUT)") (class "Default")
      (node (ref "D84") (pin "2") (pinfunction "DOUT_2") (pintype "output"))
      (node (ref "D85") (pin "4") (pinfunction "DIN_4") (pintype "input"))
    )
    (net (code "80") (name "Net-(D85-DOUT)") (class "Default")
      (node (ref "D85") (pin "2") (pinfunction "DOUT_2") (pintype "output"))
      (node (ref "D86") (pin "4") (pinfunction "DIN_4") (pintype "input"))
    )
    (net (code "81") (name "Net-(D86-DOUT)") (class "Default")
      (node (ref "D86") (pin "2") (pinfunction "DOUT_2") (pintype "output"))
      (node (ref "D87") (pin "4") (pinfunction "DIN_4") (pintype "input"))
    )
    (net (code "82") (name "Net-(D87-DOUT)") (class "Default")
      (node (ref "D87") (pin "2") (pinfunction "DOUT_2") (pintype "output"))
      (node (ref "D88") (pin "4") (pinfunction "DIN_4") (pintype "input"))
    )
    (net (code "83") (name "Net-(D89-DOUT)") (class "Default")
      (node (ref "D89") (pin "2") (pinfunction "DOUT_2") (pintype "output"))
      (node (ref "D90") (pin "4") (pinfunction "DIN_4") (pintype "input"))
    )
    (net (code "84") (name "Net-(D90-DOUT)") (class "Default")
      (node (ref "D90") (pin "2") (pinfunction "DOUT_2") (pintype "output"))
      (node (ref "D91") (pin "4") (pinfunction "DIN_4") (pintype "input"))
    )
    (net (code "85") (name "Net-(D91-DOUT)") (class "Default")
      (node (ref "D91") (pin "2") (pinfunction "DOUT_2") (pintype "output"))
      (node (ref "D92") (pin "4") (pinfunction "DIN_4") (pintype "input"))
    )
    (net (code "86") (name "Net-(D92-DOUT)") (class "Default")
      (node (ref "D92") (pin "2") (pinfunction "DOUT_2") (pintype "output"))
      (node (ref "D93") (pin "4") (pinfunction "DIN_4") (pintype "input"))
    )
    (net (code "87") (name "Net-(D93-DOUT)") (class "Default")
      (node (ref "D93") (pin "2") (pinfunction "DOUT_2") (pintype "output"))
      (node (ref "D94") (pin "4") (pinfunction "DIN_4") (pintype "input"))
    )
    (net (code "88") (name "Net-(D94-DOUT)") (class "Default")
      (node (ref "D94") (pin "2") (pinfunction "DOUT_2") (pintype "output"))
      (node (ref "D95") (pin "4") (pinfunction "DIN_4") (pintype "input"))
    )
    (net (code "89") (name "Net-(D95-DOUT)") (class "Default")
      (node (ref "D95") (pin "2") (pinfunction "DOUT_2") (pintype "output"))
      (node (ref "D96") (pin "4") (pinfunction "DIN_4") (pintype "input"))
    )
    (net (code "90") (name "Net-(D96-DOUT)") (class "Default")
      (node (ref "D96") (pin "2") (pinfunction "DOUT_2") (pintype "output"))
      (node (ref "D97") (pin "4") (pinfunction "DIN_4") (pintype "input"))
    )
    (net (code "91") (name "Net-(D97-DOUT)") (class "Default")
      (node (ref "D97") (pin "2") (pinfunction "DOUT_2") (pintype "output"))
      (node (ref "D98") (pin "4") (pinfunction "DIN_4") (pintype "input"))
    )
    (net (code "92") (name "Net-(D98-DOUT)") (class "Default")
      (node (ref "D98") (pin "2") (pinfunction "DOUT_2") (pintype "output"))
      (node (ref "D99") (pin "4") (pinfunction "DIN_4") (pintype "input"))
    )
    (net (code "93") (name "Net-(D100-DOUT)") (class "Default")
      (node (ref "D100") (pin "2") (pinfunction "DOUT_2") (pintype "output"))
      (node (ref "D101") (pin "4") (pinfunction "DIN_4") (pintype "input"))
    )
    (net (code "94") (name "Net-(D101-DOUT)") (class "Default")
      (node (ref "D101") (pin "2") (pinfunction "DOUT_2") (pintype "output"))
      (node (ref "D102") (pin "4") (pinfunction "DIN_4") (pintype "input"))
    )
    (net (code "95") (name "Net-(D102-DOUT)") (class "Default")
      (node (ref "D102") (pin "2") (pinfunction "DOUT_2") (pintype "output"))
      (node (ref "D103") (pin "4") (pinfunction "DIN_4") (pintype "input"))
    )
    (net (code "96") (name "Net-(D103-DOUT)") (class "Default")
      (node (ref "D103") (pin "2") (pinfunction "DOUT_2") (pintype "output"))
      (node (ref "D104") (pin "4") (pinfunction "DIN_4") (pintype "input"))
    )
    (net (code "97") (name "Net-(D104-DOUT)") (class "Default")
      (node (ref "D104") (pin "2") (pinfunction "DOUT_2") (pintype "output"))
      (node (ref "D105") (pin "4") (pinfunction "DIN_4") (pintype "input"))
    )
    (net (code "98") (name "Net-(D105-DOUT)") (class "Default")
      (node (ref "D105") (pin "2") (pinfunction "DOUT_2") (pintype "output"))
      (node (ref "D106") (pin "4") (pinfunction "DIN_4") (pintype "input"))
    )
    (net (code "99") (name "Net-(D106-DOUT)") (class "Default")
      (node (ref "D106") (pin "2") (pinfunction "DOUT_2") (pintype "output"))
      (node (ref "D107") (pin "4") (pinfunction "DIN_4") (pintype "input"))
    )
    (net (code "100") (name "Net-(D107-DOUT)") (class "Default")
      (node (ref "D107") (pin "2") (pinfunction "DOUT_2") (pintype "output"))
      (node (ref "D108") (pin "4") (pinfunction "DIN_4") (pintype "input"))
    )
    (net (code "101") (name "Net-(D108-DOUT)") (class "Default")
      (node (ref "D108") (pin "2") (pinfunction "DOUT_2") (pintype "output"))
      (node (ref "D109") (pin "4") (pinfunction "DIN_4") (pintype "input"))
    )
    (net (code "102") (name "Net-(D109-DOUT)") (class "Default")
      (node (ref "D109") (pin "2") (pinfunction "DOUT_2") (pintype "output"))
      (node (ref "D110") (pin "4") (pinfunction "DIN_4") (pintype "input"))
    )
    (net (code "103") (name "Net-(D111-DOUT)") (class "Default")
      (node (ref "D111") (pin "2") (pinfunction "DOUT_2") (pintype "output"))
      (node (ref "D112") (pin "4") (pinfunction "DIN_4") (pintype "input"))
    )
    (net (code "104") (name "Net-(D112-DOUT)") (class "Default")
      (node (ref "D112") (pin "2") (pinfunction "DOUT_2") (pintype "output"))
      (node (ref "D113") (pin "4") (pinfunction "DIN_4") (pintype "input"))
    )
    (net (code "105") (name "Net-(D113-DOUT)") (class "Default")
      (node (ref "D113") (pin "2") (pinfunction "DOUT_2") (pintype "output"))
      (node (ref "D114") (pin "4") (pinfunction "DIN_4") (pintype "input"))
    )
    (net (code "106") (name "Net-(D114-DOUT)") (class "Default")
      (node (ref "D114") (pin "2") (pinfunction "DOUT_2") (pintype "output"))
      (node (ref "D115") (pin "4") (pinfunction "DIN_4") (pintype "input"))
    )
    (net (code "107") (name "Net-(D115-DOUT)") (class "Default")
      (node (ref "D115") (pin "2") (pinfunction "DOUT_2") (pintype "output"))
      (node (ref "D116") (pin "4") (pinfunction "DIN_4") (pintype "input"))
    )
    (net (code "108") (name "Net-(D116-DOUT)") (class "Default")
      (node (ref "D116") (pin "2") (pinfunction "DOUT_2") (pintype "output"))
      (node (ref "D117") (pin "4") (pinfunction "DIN_4") (pintype "input"))
    )
    (net (code "109") (name "Net-(D117-DOUT)") (class "Default")
      (node (ref "D117") (pin "2") (pinfunction "DOUT_2") (pintype "output"))
      (node (ref "D118") (pin "4") (pinfunction "DIN_4") (pintype "input"))
    )
    (net (code "110") (name "Net-(D118-DOUT)") (class "Default")
      (node (ref "D118") (pin "2") (pinfunction "DOUT_2") (pintype "output"))
      (node (ref "D119") (pin "4") (pinfunction "DIN_4") (pintype "input"))
    )
    (net (code "111") (name "Net-(D119-DOUT)") (class "Default")
      (node (ref "D119") (pin "2") (pinfunction "DOUT_2") (pintype "output"))
      (node (ref "D120") (pin "4") (pinfunction "DIN_4") (pintype "input"))
    )
    (net (code "112") (name "Net-(D120-DOUT)") (class "Default")
      (node (ref "D120") (pin "2") (pinfunction "DOUT_2") (pintype "output"))
      (node (ref "D121") (pin "4") (pinfunction "DIN_4") (pintype "input"))
    )
    (net (code "113") (name "ROW1_DIN") (class "Default")
      (node (ref "D1") (pin "4") (pinfunction "DIN_4") (pintype "input"))
      (node (ref "P1") (pin "3") (pinfunction "3_3") (pintype "passive"))
    )
    (net (code "114") (name "ROW1_DOUT") (class "Default")
      (node (ref "D11") (pin "2") (pinfunction "DOUT_2") (pintype "output"))
      (node (ref "D12") (pin "4") (pinfunction "DIN_4") (pintype "input"))
    )
    (net (code "115") (name "ROW2_DOUT") (class "Default")
      (node (ref "D22") (pin "2") (pinfunction "DOUT_2") (pintype "output"))
      (node (ref "D23") (pin "4") (pinfunction "DIN_4") (pintype "input"))
    )
    (net (code "116") (name "ROW3_DOUT") (class "Default")
      (node (ref "D33") (pin "2") (pinfunction "DOUT_2") (pintype "output"))
      (node (ref "D34") (pin "4") (pinfunction "DIN_4") (pintype "input"))
    )
    (net (code "117") (name "ROW4_DOUT") (class "Default")
      (node (ref "D44") (pin "2") (pinfunction "DOUT_2") (pintype "output"))
      (node (ref "D45") (pin "4") (pinfunction "DIN_4") (pintype "input"))
    )
    (net (code "118") (name "ROW5_DOUT") (class "Default")
      (node (ref "D55") (pin "2") (pinfunction "DOUT_2") (pintype "output"))
      (node (ref "D56") (pin "4") (pinfunction "DIN_4") (pintype "input"))
    )
    (net (code "119") (name "ROW6_DOUT") (class "Default")
      (node (ref "D66") (pin "2") (pinfunction "DOUT_2") (pintype "output"))
      (node (ref "D67") (pin "4") (pinfunction "DIN_4") (pintype "input"))
    )
    (net (code "120") (name "ROW7_DOUT") (class "Default")
      (node (ref "D77") (pin "2") (pinfunction "DOUT_2") (pintype "output"))
      (node (ref "D78") (pin "4") (pinfunction "DIN_4") (pintype "input"))
    )
    (net (code "121") (name "ROW8_DOUT") (class "Default")
      (node (ref "D88") (pin "2") (pinfunction "DOUT_2") (pintype "output"))
      (node (ref "D89") (pin "4") (pinfunction "DIN_4") (pintype "input"))
    )
    (net (code "122") (name "ROW9_DOUT") (class "Default")
      (node (ref "D100") (pin "4") (pinfunction "DIN_4") (pintype "input"))
      (node (ref "D99") (pin "2") (pinfunction "DOUT_2") (pintype "output"))
    )
    (net (code "123") (name "ROW10_DOUT") (class "Default")
      (node (ref "D110") (pin "2") (pinfunction "DOUT_2") (pintype "output"))
      (node (ref "D111") (pin "4") (pinfunction "DIN_4") (pintype "input"))
    )
    (net (code "124") (name "ROW11_DOUT") (class "Default")
      (node (ref "D121") (pin "2") (pinfunction "DOUT_2") (pintype "output"))
    )
  )
)
